# transponder-5_2.net
KiCad netlist of a schematic drawn in EAGLE
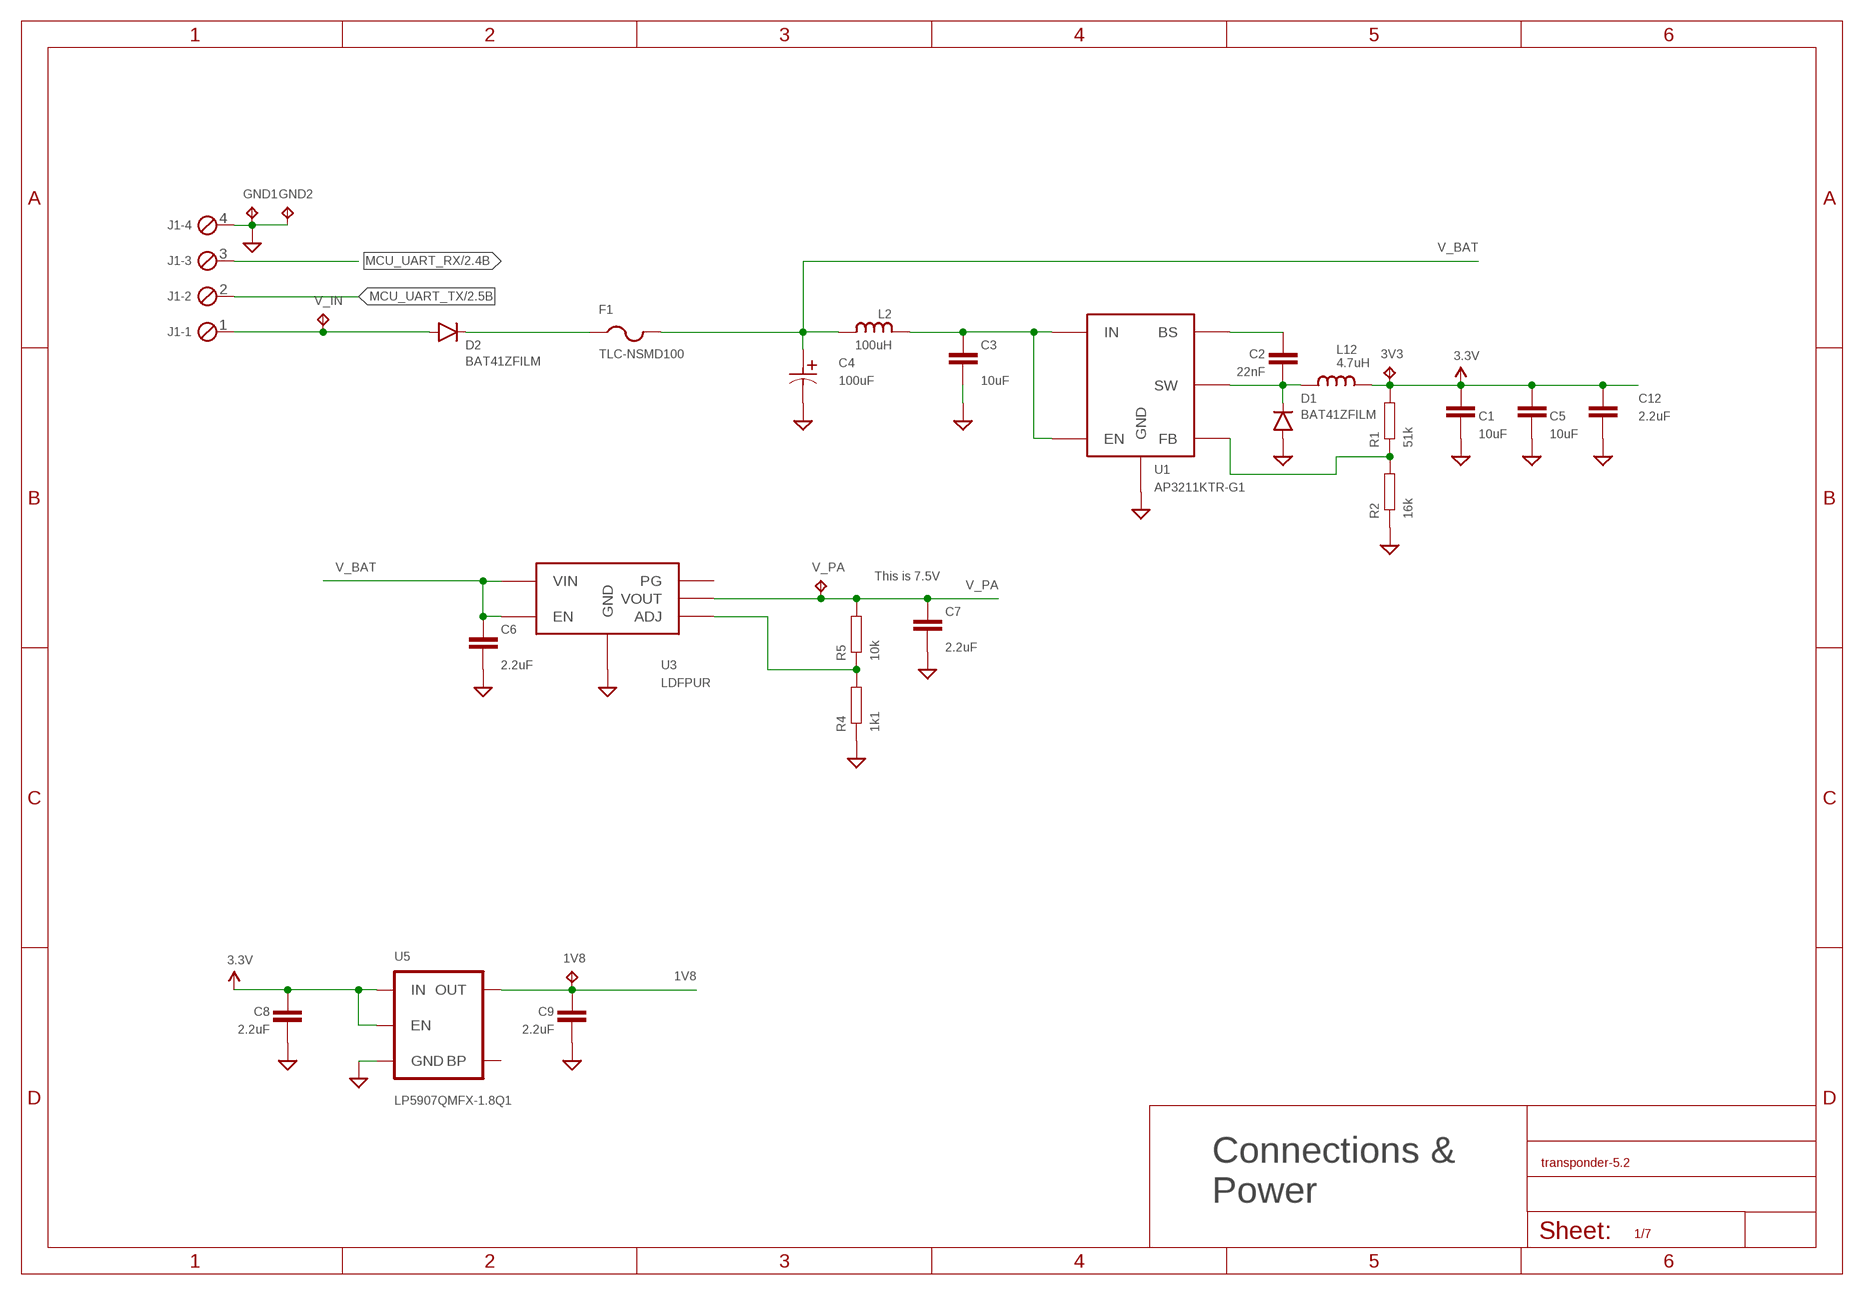
[diagram p0: schematic, sheet 1]
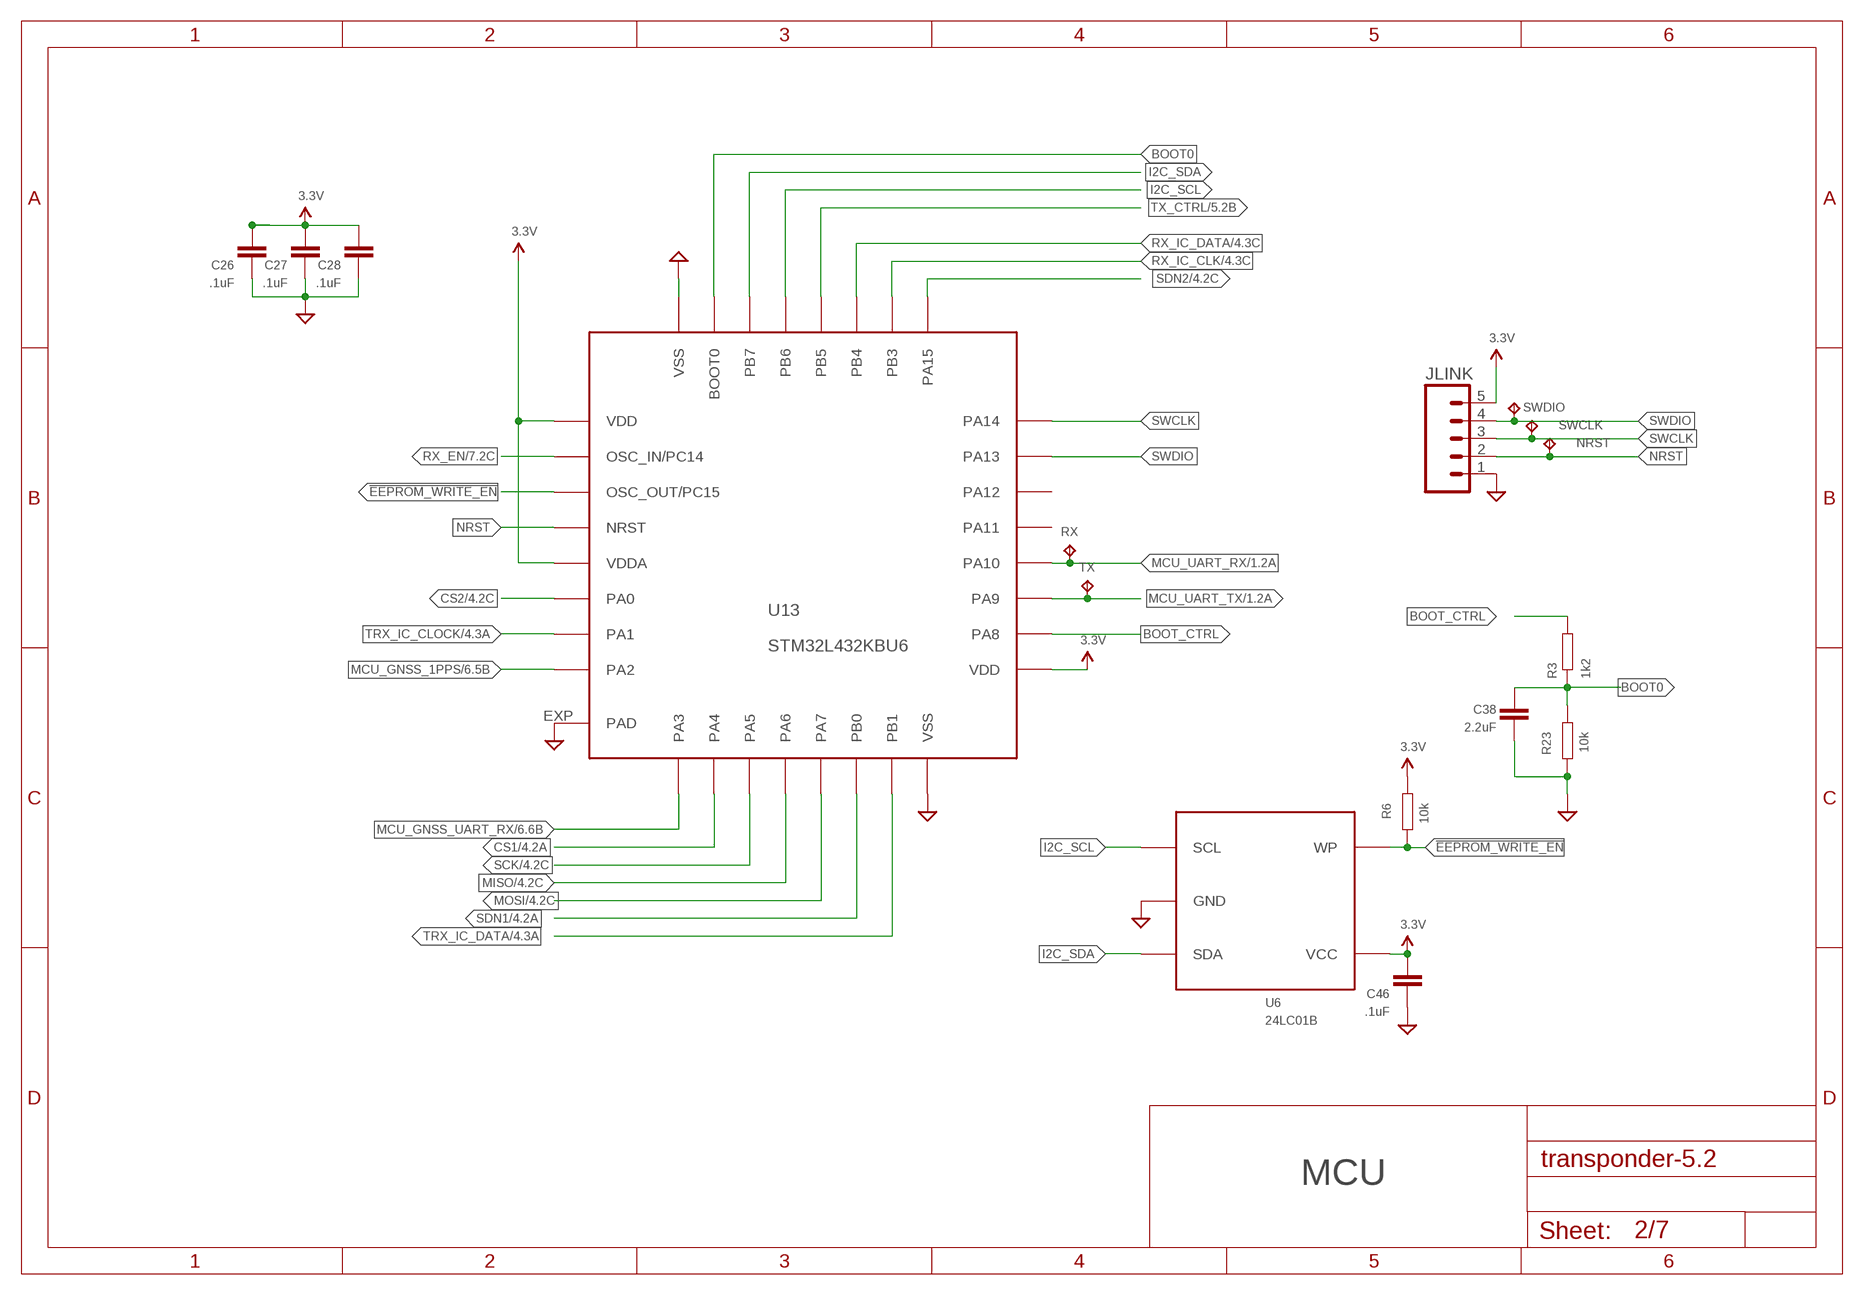
[diagram p1: schematic, sheet 2]
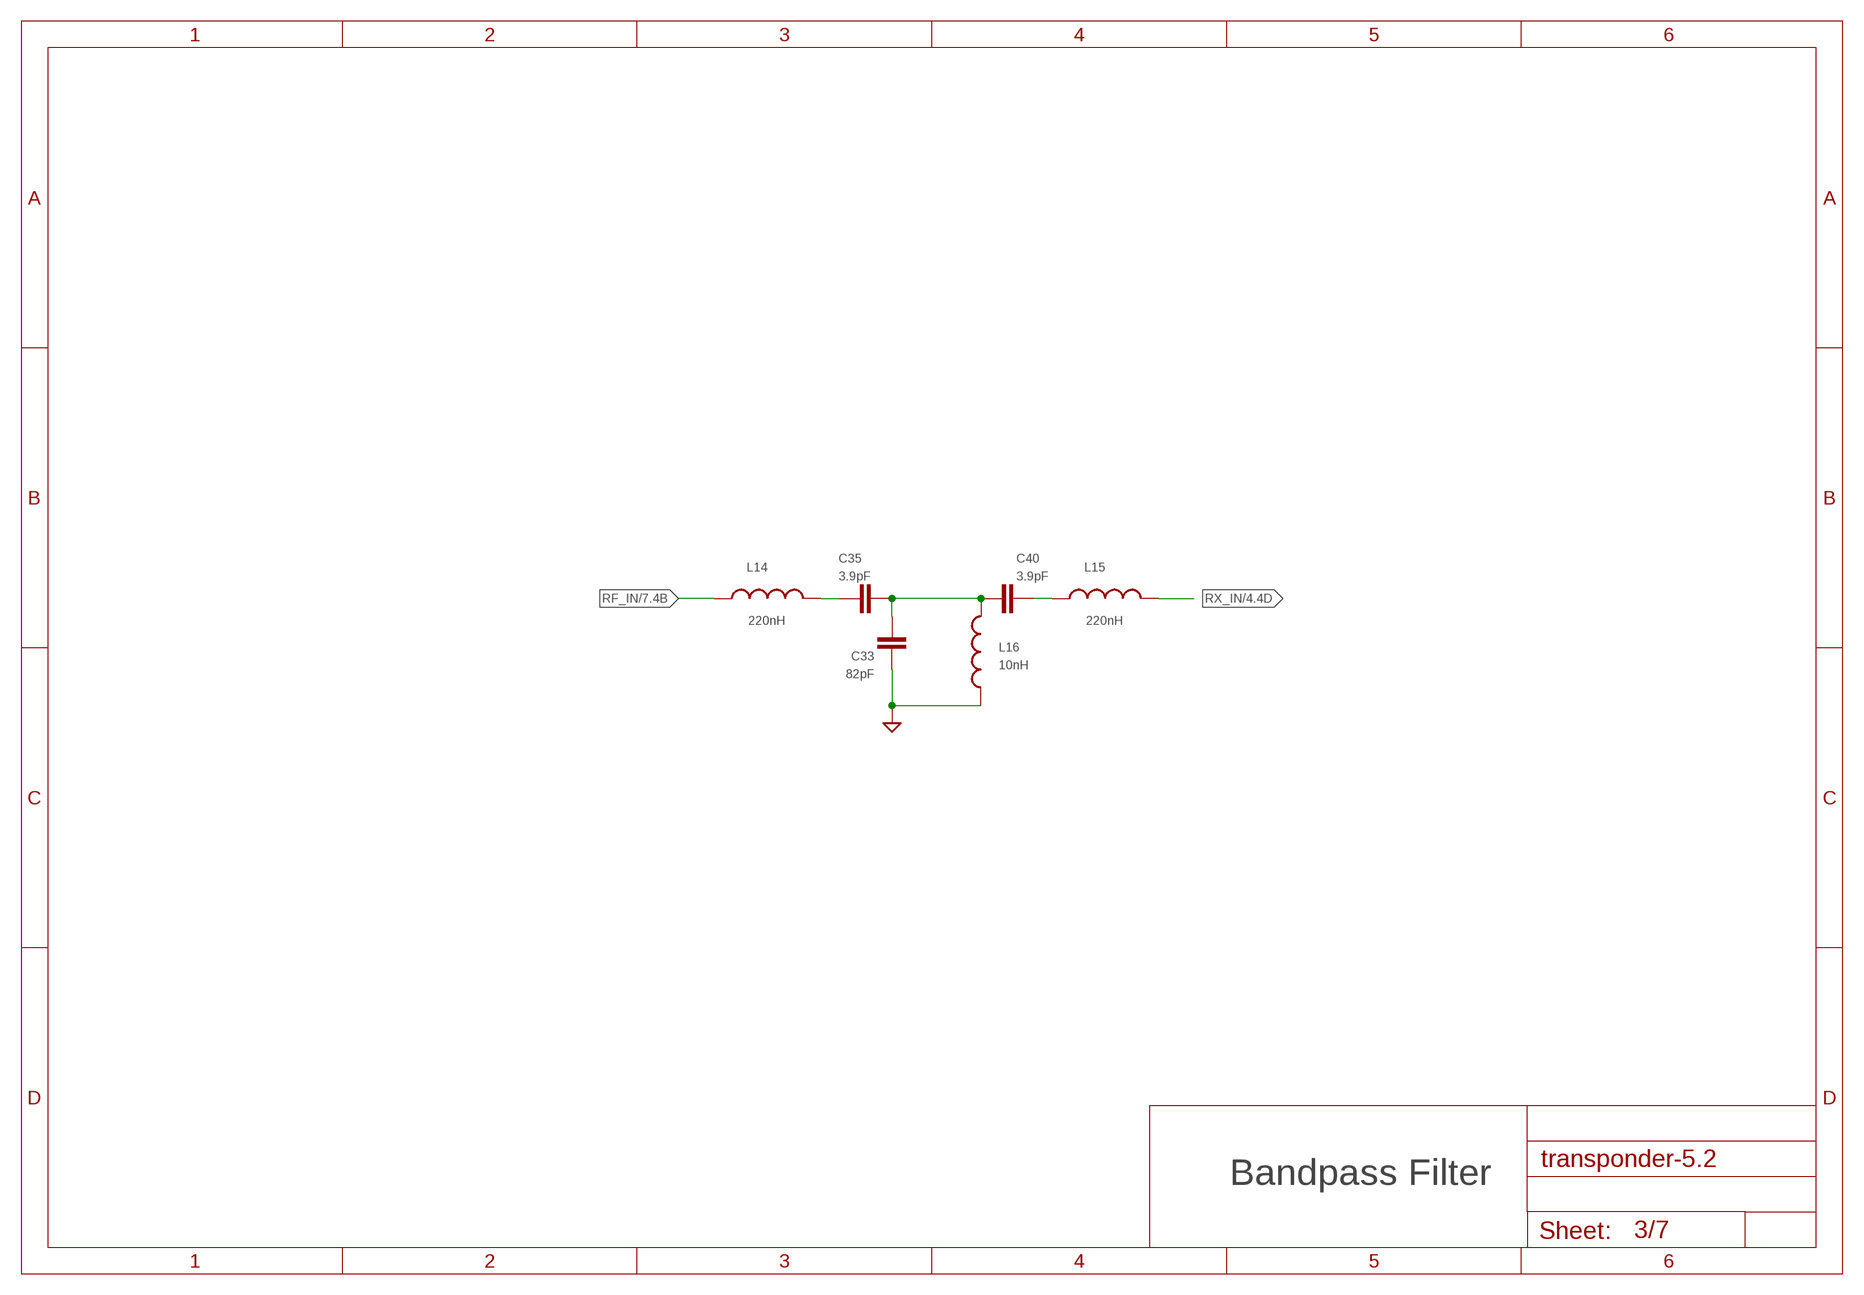
[diagram p2: schematic, sheet 3]
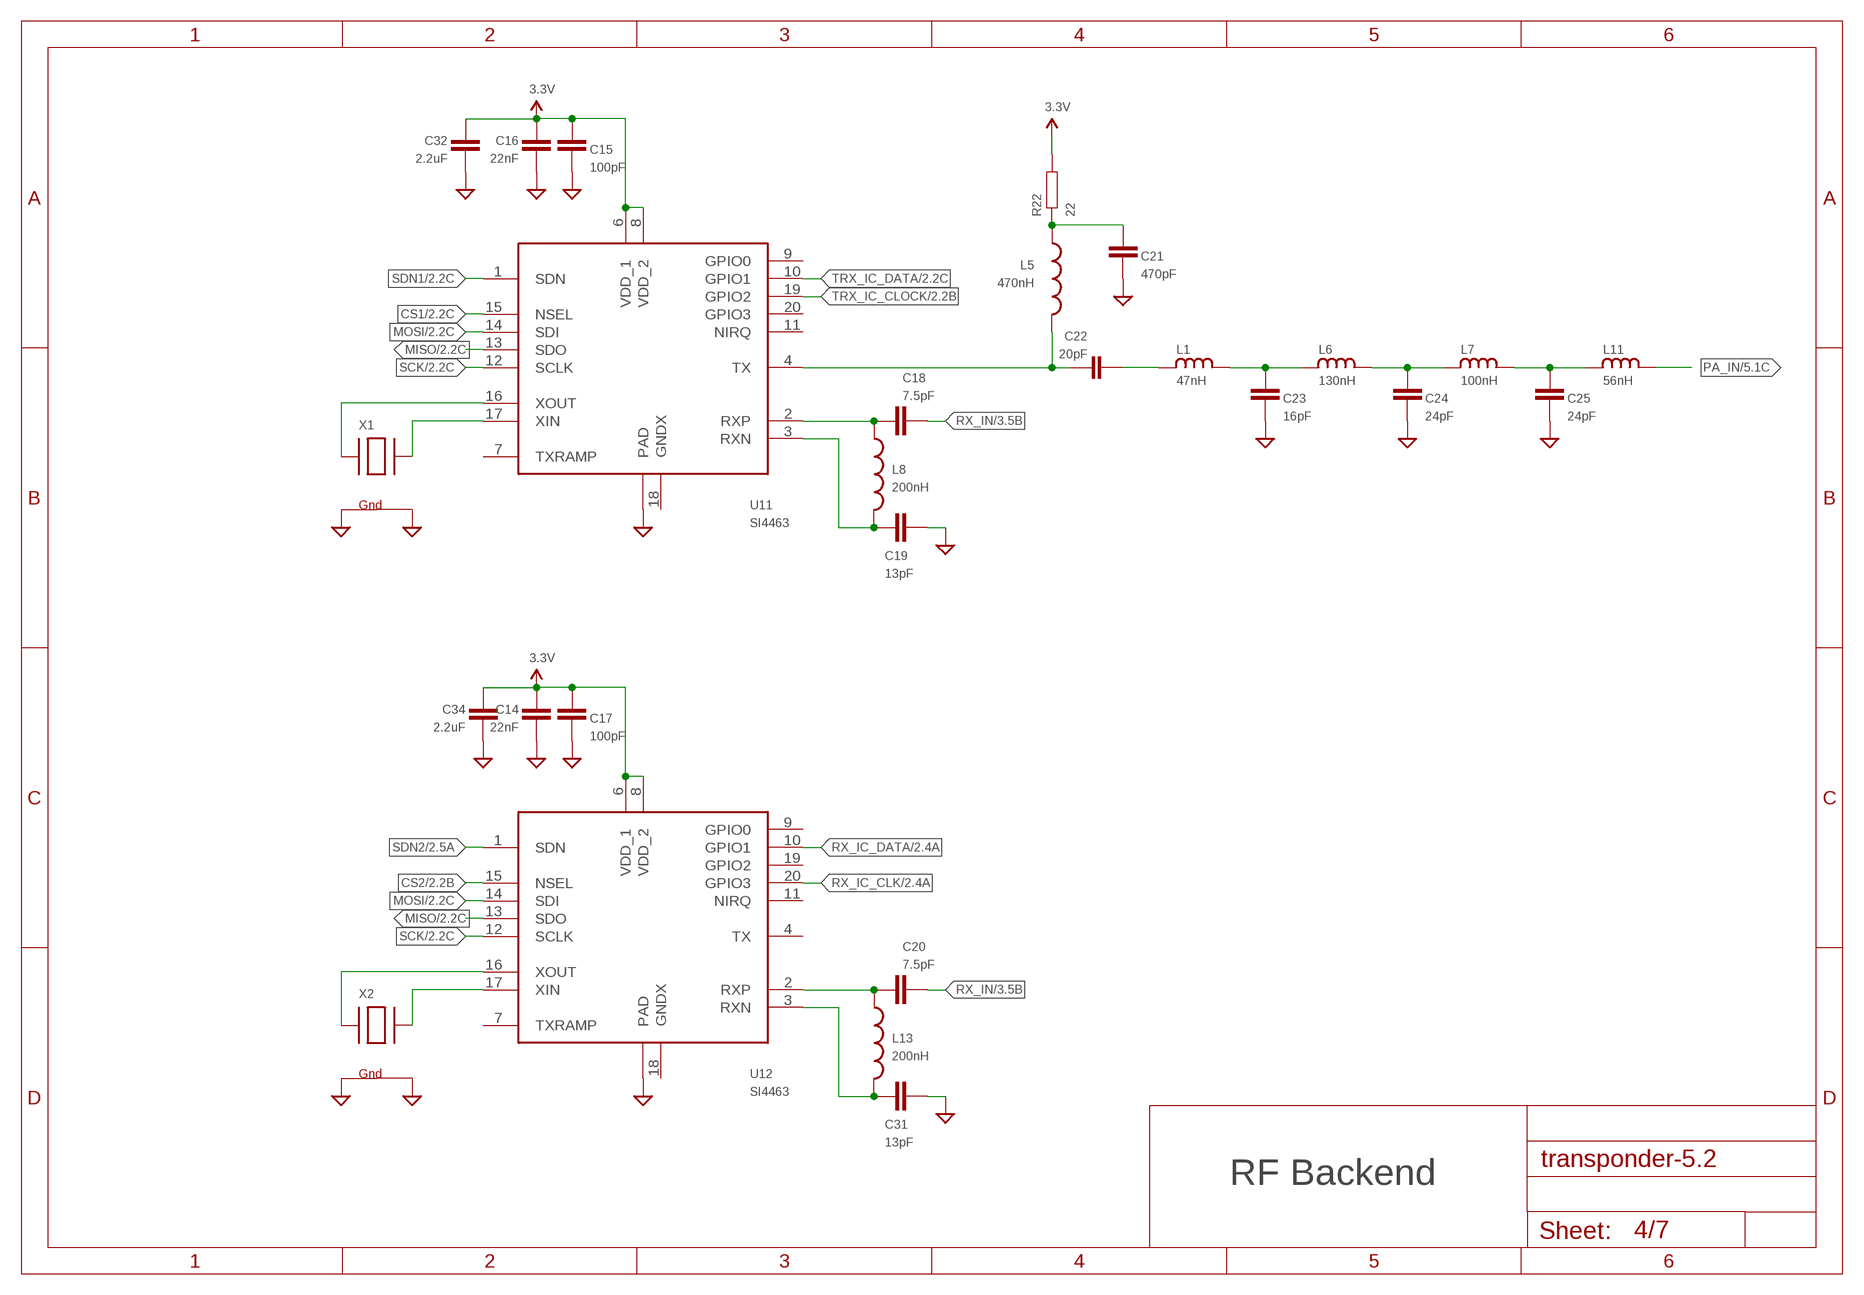
[diagram p3: schematic, sheet 4]
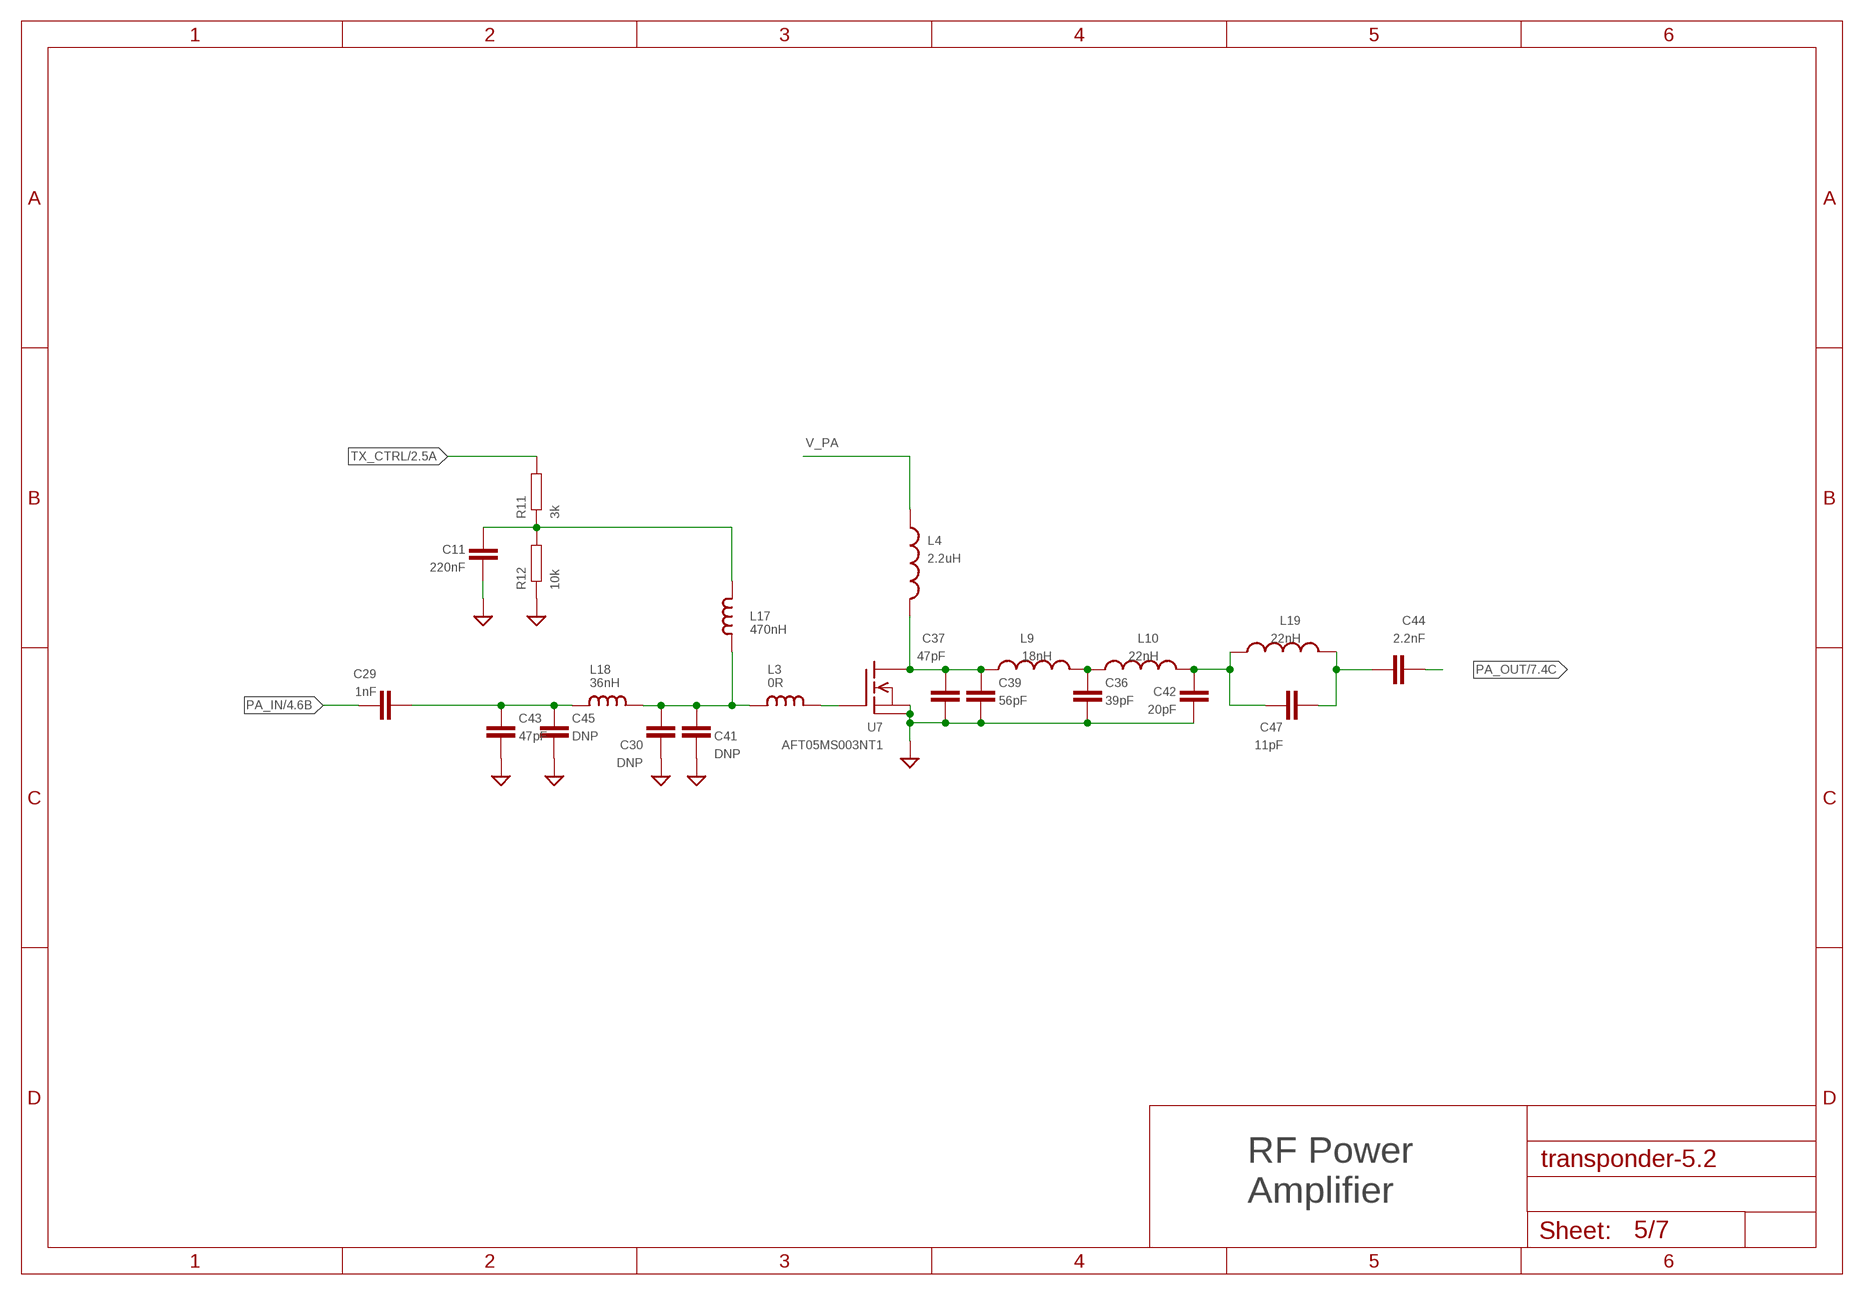
[diagram p4: schematic, sheet 5]
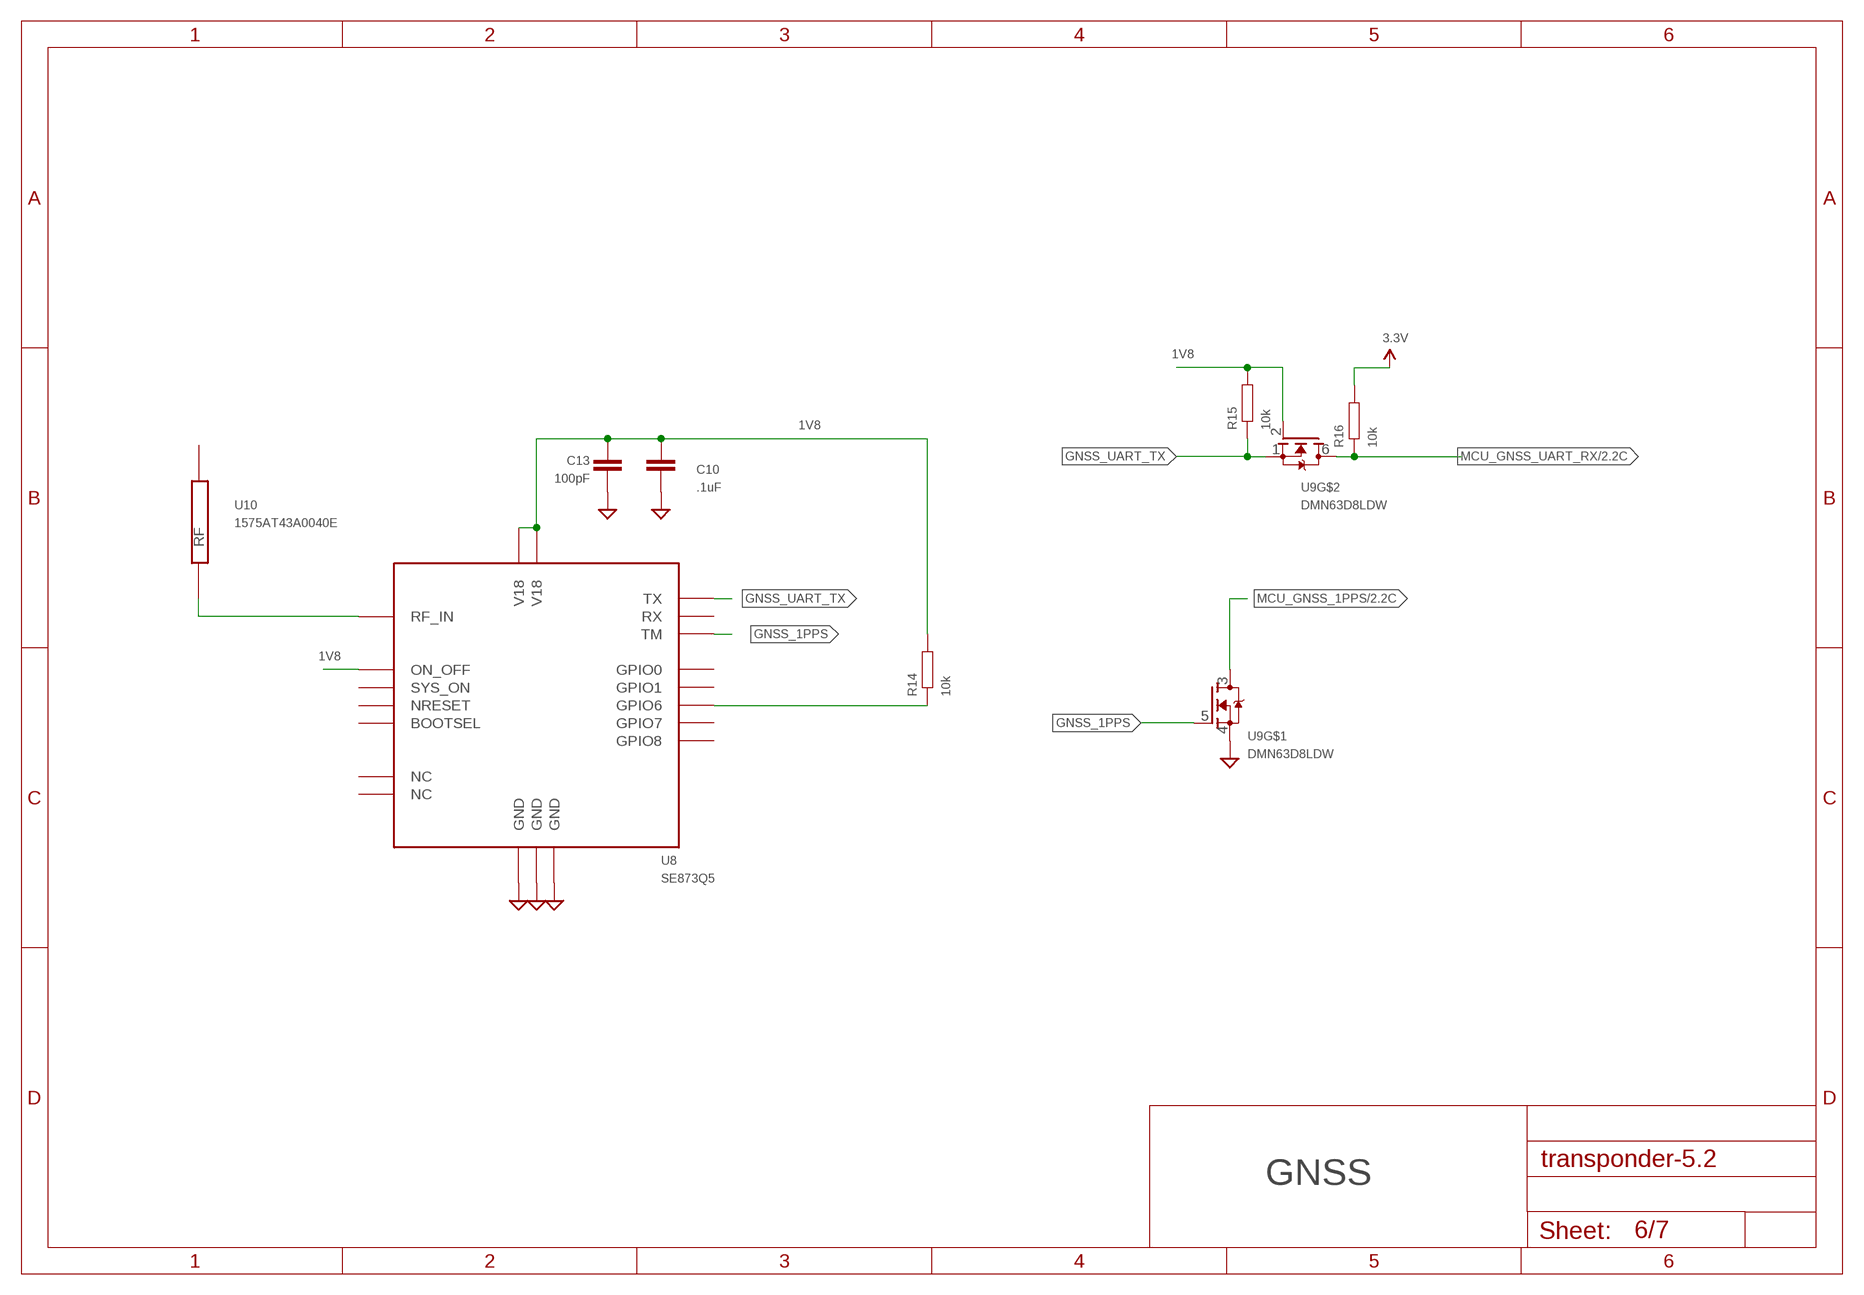
[diagram p5: schematic, sheet 6]
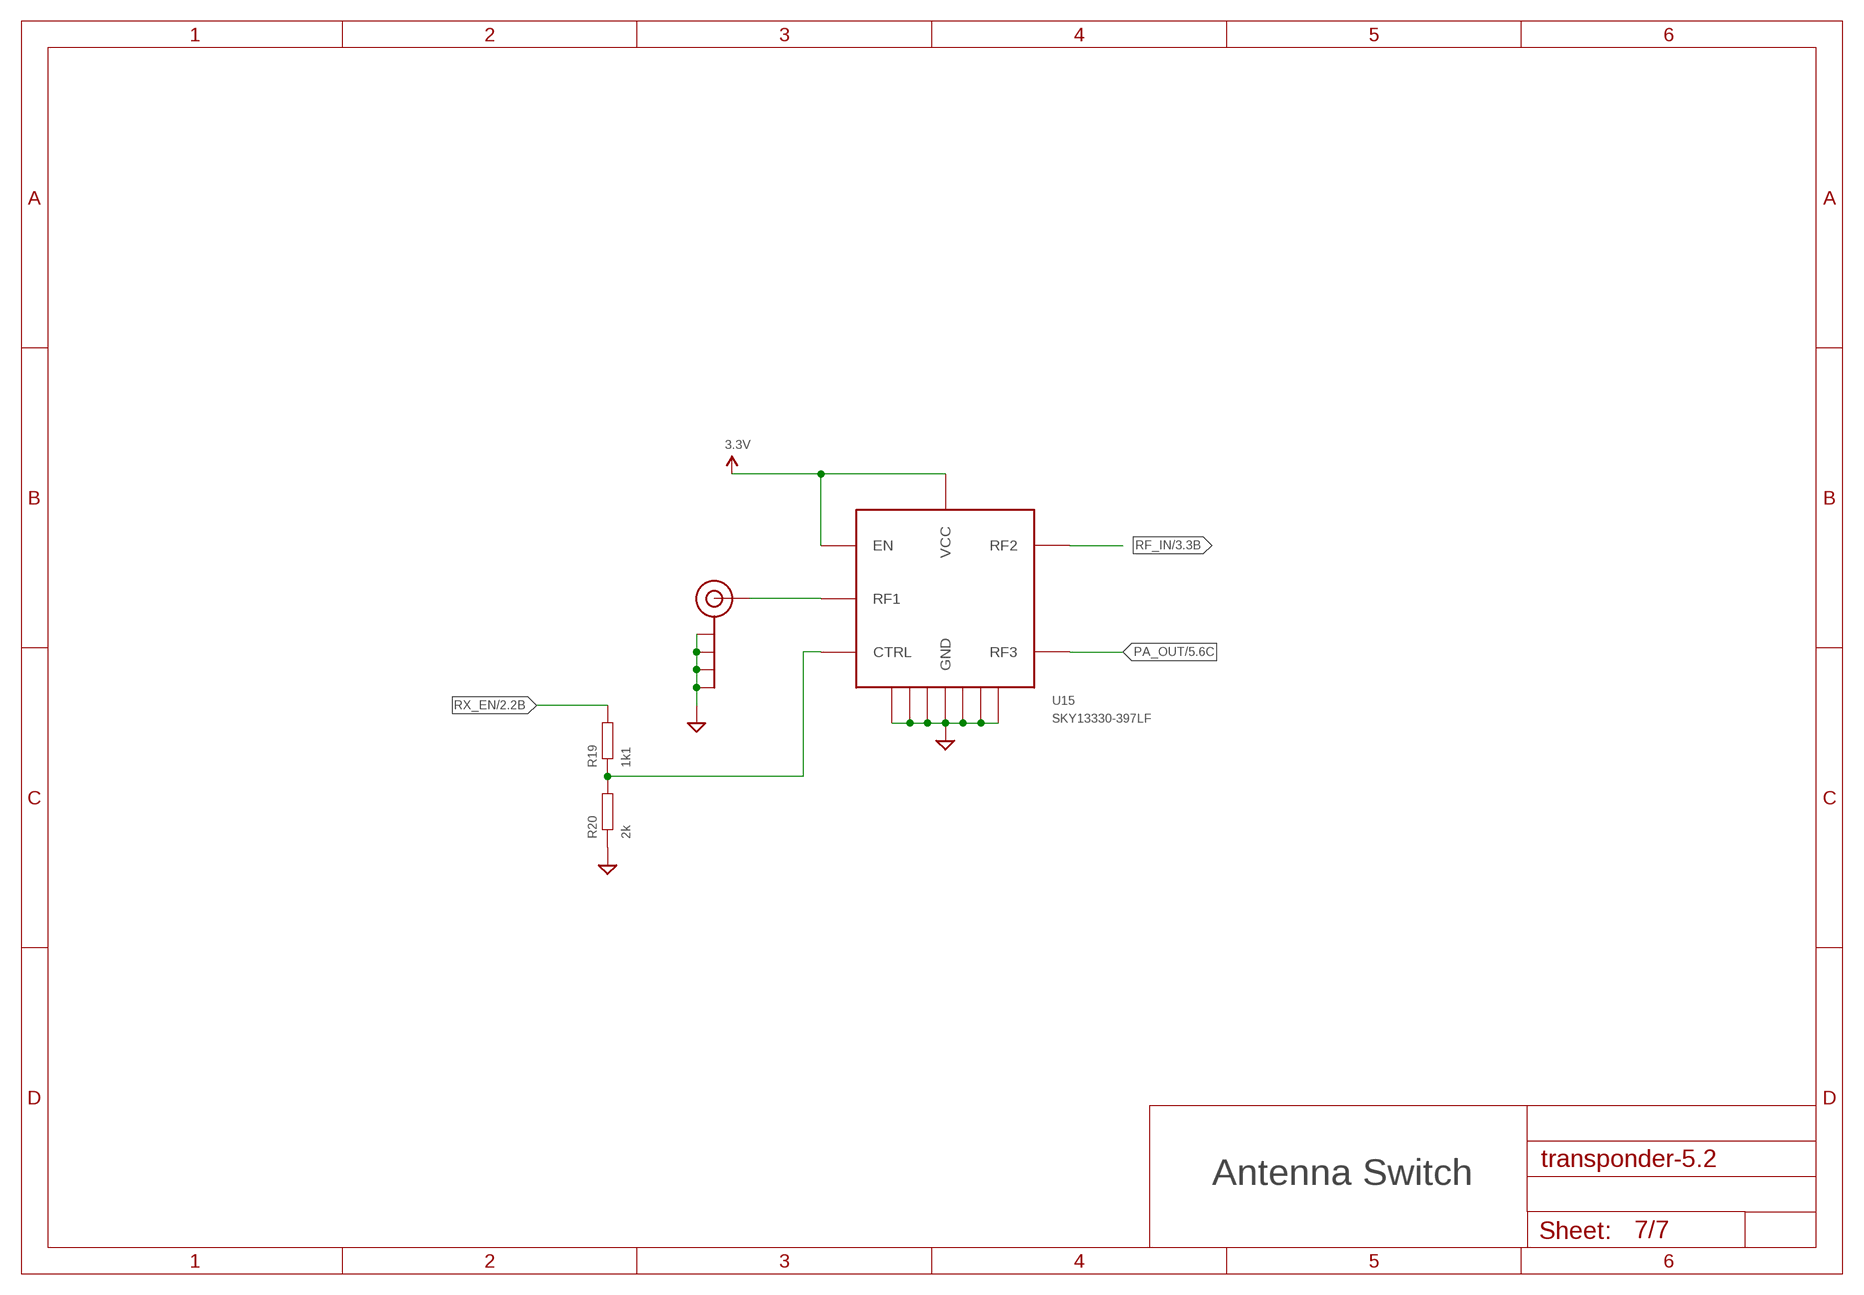
[diagram p6: schematic, sheet 7]

(export (version "E")
  (design (tool "Eeschema 10.0.6"))
  (components
    (comp (ref "J$1")
      (value "SMA_EDGE")
      (footprint "eagle-import:SMA-EDGE")
      (libsource (lib "eagle-import") (part "SMA_EDGE"))
    )
    (comp (ref "R19")
      (value "1k1")
      (footprint "eagle-import:0603-RES")
      (libsource (lib "eagle-import") (part "RESISTOR0603-RES"))
    )
    (comp (ref "R20")
      (value "2k")
      (footprint "eagle-import:0603-RES")
      (fields (field (name "PARTNO") "RC0603FR-072KL"))
      (libsource (lib "eagle-import") (part "RESISTOR0603-RES"))
    )
    (comp (ref "U15")
      (value "SKY13330-397LF")
      (footprint "eagle-import:QFN12")
      (libsource (lib "eagle-import") (part "SKYWORKS-13330397LF"))
    )
    (comp (ref "C33")
      (value "82pF")
      (footprint "eagle-import:0603-CAP")
      (libsource (lib "eagle-import") (part "CAP0603-CAP"))
    )
    (comp (ref "C35")
      (value "3.9pF")
      (footprint "eagle-import:0603-CAP")
      (fields (field (name "PARTNO") "GCM1885C2A3R9BA16D"))
      (libsource (lib "eagle-import") (part "CAP0603-CAP"))
    )
    (comp (ref "C40")
      (value "3.9pF")
      (footprint "eagle-import:0603-CAP")
      (fields (field (name "PARTNO") "GCM1885C2A3R9BA16D"))
      (libsource (lib "eagle-import") (part "CAP0603-CAP"))
    )
    (comp (ref "L14")
      (value "220nH")
      (footprint "eagle-import:0603")
      (libsource (lib "eagle-import") (part "SparkFun-Passives_INDUCTOR0603"))
    )
    (comp (ref "L15")
      (value "220nH")
      (footprint "eagle-import:0603")
      (libsource (lib "eagle-import") (part "SparkFun-Passives_INDUCTOR0603"))
    )
    (comp (ref "L16")
      (value "10nH")
      (footprint "eagle-import:0603")
      (fields (field (name "PARTNO") "LQW18AS10NJ0CD"))
      (libsource (lib "eagle-import") (part "SparkFun-Passives_INDUCTOR0603"))
    )
    (comp (ref "C10")
      (value ".1uF")
      (footprint "eagle-import:0603-CAP")
      (fields (field (name "PARTNO") "EMK107B7104KAHT"))
      (libsource (lib "eagle-import") (part "CAP0603-CAP"))
    )
    (comp (ref "C13")
      (value "100pF")
      (footprint "eagle-import:0603-CAP")
      (fields (field (name "PARTNO") "GCM1885C2A101JA16D"))
      (libsource (lib "eagle-import") (part "CAP0603-CAP"))
    )
    (comp (ref "R14")
      (value "10k")
      (footprint "eagle-import:0603-RES")
      (fields (field (name "PARTNO") "RC0603JR-0710KL"))
      (libsource (lib "eagle-import") (part "RESISTOR0603-RES"))
    )
    (comp (ref "R15")
      (value "10k")
      (footprint "eagle-import:0603-RES")
      (fields (field (name "PARTNO") "RC0603JR-0710KL"))
      (libsource (lib "eagle-import") (part "RESISTOR0603-RES"))
    )
    (comp (ref "R16")
      (value "10k")
      (footprint "eagle-import:0603-RES")
      (fields (field (name "PARTNO") "RC0603JR-0710KL"))
      (libsource (lib "eagle-import") (part "RESISTOR0603-RES"))
    )
    (comp (ref "U8")
      (value "SE873Q5")
      (footprint "eagle-import:SE873")
      (libsource (lib "eagle-import") (part "SE873"))
    )
    (comp (ref "U9")
      (value "DMN63D8LDW")
      (footprint "eagle-import:SOT363")
      (fields (field (name "PARTNO") "DMN63D8LDW"))
      (libsource (lib "eagle-import") (part "DMN63D8LDW"))
    )
    (comp (ref "U10")
      (value "1575AT43A0040E")
      (footprint "eagle-import:1575AT43A0040E")
      (libsource (lib "eagle-import") (part "1575AT43A0040E"))
    )
    (comp (ref "C11")
      (value "220nF")
      (footprint "eagle-import:0603-CAP")
      (libsource (lib "eagle-import") (part "CAP0603-CAP"))
    )
    (comp (ref "C29")
      (value "1nF")
      (footprint "eagle-import:0603-CAP")
      (fields (field (name "PARTNO") "GRM1885C1H102JA01D"))
      (libsource (lib "eagle-import") (part "CAP0603-CAP"))
    )
    (comp (ref "C30")
      (value "DNP")
      (footprint "eagle-import:0603-CAP")
      (fields (field (name "PARTNO") "GCM1885C2A101JA16D"))
      (libsource (lib "eagle-import") (part "CAP0603-CAP"))
    )
    (comp (ref "C36")
      (value "39pF")
      (footprint "eagle-import:0603-CAP")
      (fields (field (name "PARTNO") "GRM1885C1H390JA01D"))
      (libsource (lib "eagle-import") (part "CAP0603-CAP"))
    )
    (comp (ref "C37")
      (value "47pF")
      (footprint "eagle-import:0603-CAP")
      (libsource (lib "eagle-import") (part "CAP0603-CAP"))
    )
    (comp (ref "C39")
      (value "56pF")
      (footprint "eagle-import:0603-CAP")
      (fields (field (name "PARTNO") "GRM1885C1H560JA01D"))
      (libsource (lib "eagle-import") (part "CAP0603-CAP"))
    )
    (comp (ref "C41")
      (value "DNP")
      (footprint "eagle-import:0603-CAP")
      (fields (field (name "PARTNO") "Murata Electronics"))
      (libsource (lib "eagle-import") (part "CAP0603-CAP"))
    )
    (comp (ref "C42")
      (value "20pF")
      (footprint "eagle-import:0603-CAP")
      (fields (field (name "PARTNO") "GRM1885C1H200JA01D"))
      (libsource (lib "eagle-import") (part "CAP0603-CAP"))
    )
    (comp (ref "C43")
      (value "47pF")
      (footprint "eagle-import:0603-CAP")
      (libsource (lib "eagle-import") (part "CAP0603-CAP"))
    )
    (comp (ref "C44")
      (value "2.2nF")
      (footprint "eagle-import:0603-CAP")
      (fields (field (name "PARTNO") "GRM1885C1H222JA01J"))
      (libsource (lib "eagle-import") (part "CAP0603-CAP"))
    )
    (comp (ref "C45")
      (value "DNP")
      (footprint "eagle-import:0603-CAP")
      (fields (field (name "PARTNO") "GRM1885C1H560JA01D"))
      (libsource (lib "eagle-import") (part "CAP0603-CAP"))
    )
    (comp (ref "C47")
      (value "11pF")
      (footprint "eagle-import:0603-CAP")
      (fields (field (name "PARTNO") "GRM1885C1H110JA01D"))
      (libsource (lib "eagle-import") (part "CAP0603-CAP"))
    )
    (comp (ref "L3")
      (value "0R")
      (footprint "eagle-import:0603")
      (fields (field (name "PARTNO") "LQW18AN11NJ00D"))
      (libsource (lib "eagle-import") (part "INDUCTOR0603"))
    )
    (comp (ref "L4")
      (value "2.2uH")
      (footprint "eagle-import:0805")
      (fields (field (name "PARTNO") "BRC2012T2R2MD"))
      (libsource (lib "eagle-import") (part "SparkFun-Passives_INDUCTOR0805"))
    )
    (comp (ref "L9")
      (value "18nH")
      (footprint "eagle-import:0603")
      (fields (field (name "PARTNO") "LQW18AN18NG00D"))
      (libsource (lib "eagle-import") (part "SparkFun-Passives_INDUCTOR0603"))
    )
    (comp (ref "L10")
      (value "22nH")
      (footprint "eagle-import:0603")
      (fields (field (name "PARTNO") "LQW18AN22NJ00D"))
      (libsource (lib "eagle-import") (part "SparkFun-Passives_INDUCTOR0603"))
    )
    (comp (ref "L17")
      (value "470nH")
      (footprint "eagle-import:0603")
      (fields (field (name "PARTNO") "HK1608R47J-T"))
      (libsource (lib "eagle-import") (part "INDUCTOR0603"))
    )
    (comp (ref "L18")
      (value "36nH")
      (footprint "eagle-import:0603")
      (libsource (lib "eagle-import") (part "INDUCTOR0603"))
    )
    (comp (ref "L19")
      (value "22nH")
      (footprint "eagle-import:0603")
      (fields (field (name "PARTNO") "LQW18AN22NJ00D"))
      (libsource (lib "eagle-import") (part "SparkFun-Passives_INDUCTOR0603"))
    )
    (comp (ref "R11")
      (value "3k")
      (footprint "eagle-import:0603-RES")
      (libsource (lib "eagle-import") (part "RESISTOR0603-RES"))
    )
    (comp (ref "R12")
      (value "10k")
      (footprint "eagle-import:0603-RES")
      (fields (field (name "PARTNO") "RC0603JR-0710KL"))
      (libsource (lib "eagle-import") (part "RESISTOR0603-RES"))
    )
    (comp (ref "U7")
      (value "AFT05MS003NT1")
      (footprint "eagle-import:SOT-89")
      (libsource (lib "eagle-import") (part "AFT0SMS003N"))
    )
    (comp (ref "C26")
      (value ".1uF")
      (footprint "eagle-import:0603-CAP")
      (fields (field (name "PARTNO") "EMK107B7104KAHT"))
      (libsource (lib "eagle-import") (part "CAP0603-CAP"))
    )
    (comp (ref "C27")
      (value ".1uF")
      (footprint "eagle-import:0603-CAP")
      (fields (field (name "PARTNO") "EMK107B7104KAHT"))
      (libsource (lib "eagle-import") (part "CAP0603-CAP"))
    )
    (comp (ref "C28")
      (value ".1uF")
      (footprint "eagle-import:0603-CAP")
      (fields (field (name "PARTNO") "EMK107B7104KAHT"))
      (libsource (lib "eagle-import") (part "CAP0603-CAP"))
    )
    (comp (ref "C38")
      (value "2.2uF")
      (footprint "eagle-import:0603-CAP")
      (fields (field (name "PARTNO") "EMK107BJ225KA-T"))
      (libsource (lib "eagle-import") (part "CAP0603-CAP"))
    )
    (comp (ref "C46")
      (value ".1uF")
      (footprint "eagle-import:0603-CAP")
      (fields (field (name "PARTNO") "EMK107B7104KAHT"))
      (libsource (lib "eagle-import") (part "CAP0603-CAP"))
    )
    (comp (ref "JLINK")
      (value "M05PTH")
      (footprint "eagle-import:1X05")
      (libsource (lib "eagle-import") (part "M05PTH"))
    )
    (comp (ref "NRST")
      (value "TPTP16R")
      (footprint "eagle-import:TP16R")
      (libsource (lib "eagle-import") (part "TPTP16R"))
    )
    (comp (ref "R3")
      (value "1k2")
      (footprint "eagle-import:0603-RES")
      (fields (field (name "PARTNO") "RC0603JR-071K2L"))
      (libsource (lib "eagle-import") (part "RESISTOR0603-RES"))
    )
    (comp (ref "R6")
      (value "10k")
      (footprint "eagle-import:0603-RES")
      (fields (field (name "PARTNO") "RC0603JR-0710KL"))
      (libsource (lib "eagle-import") (part "RESISTOR0603-RES"))
    )
    (comp (ref "R23")
      (value "10k")
      (footprint "eagle-import:0603-RES")
      (fields (field (name "PARTNO") "RC0603JR-0710KL"))
      (libsource (lib "eagle-import") (part "RESISTOR0603-RES"))
    )
    (comp (ref "RX")
      (value "TPTP16R")
      (footprint "eagle-import:TP16R")
      (libsource (lib "eagle-import") (part "TPTP16R"))
    )
    (comp (ref "SWCLK")
      (value "TPTP16R")
      (footprint "eagle-import:TP16R")
      (libsource (lib "eagle-import") (part "TPTP16R"))
    )
    (comp (ref "SWDIO")
      (value "TPTP16R")
      (footprint "eagle-import:TP16R")
      (libsource (lib "eagle-import") (part "TPTP16R"))
    )
    (comp (ref "TX")
      (value "TPTP16R")
      (footprint "eagle-import:TP16R")
      (libsource (lib "eagle-import") (part "TPTP16R"))
    )
    (comp (ref "U6")
      (value "24LC01B")
      (footprint "eagle-import:SOT23-5")
      (fields (field (name "PARTNO") "24LC01BT-I/OT"))
      (libsource (lib "eagle-import") (part "24LC01B"))
    )
    (comp (ref "U13")
      (value "STM32L432KBU6")
      (footprint "eagle-import:QFN32")
      (fields (field (name "PARTNO") "STM32L431KBU6"))
      (libsource (lib "eagle-import") (part "STM32L432KXXX"))
    )
    (comp (ref "1V8")
      (value "TPTP16R")
      (footprint "eagle-import:TP16R")
      (libsource (lib "eagle-import") (part "TPTP16R"))
    )
    (comp (ref "3V3")
      (value "TPTP16R")
      (footprint "eagle-import:TP16R")
      (libsource (lib "eagle-import") (part "TPTP16R"))
    )
    (comp (ref "C1")
      (value "10uF")
      (footprint "eagle-import:0805")
      (fields (field (name "PARTNO") " EMK212ABJ106KG-T"))
      (libsource (lib "eagle-import") (part "CAP0805"))
    )
    (comp (ref "C2")
      (value "22nF")
      (footprint "eagle-import:0603-CAP")
      (fields (field (name "PARTNO") "GRM188R71E223KA01D"))
      (libsource (lib "eagle-import") (part "CAP0603-CAP"))
    )
    (comp (ref "C3")
      (value "10uF")
      (footprint "eagle-import:0805")
      (fields (field (name "PARTNO") " EMK212ABJ106KG-T"))
      (libsource (lib "eagle-import") (part "CAP0805"))
    )
    (comp (ref "C4")
      (value "100uF")
      (footprint "eagle-import:PCAP_6.3X5.4-ELECT")
      (fields (field (name "MF") "Nichicon") (field (name "MP") "UWX1C101MCL1GB"))
      (libsource (lib "eagle-import") (part "UWX1C101MCL1GB"))
    )
    (comp (ref "C5")
      (value "10uF")
      (footprint "eagle-import:0805")
      (fields (field (name "PARTNO") " EMK212ABJ106KG-T"))
      (libsource (lib "eagle-import") (part "CAP0805"))
    )
    (comp (ref "C6")
      (value "2.2uF")
      (footprint "eagle-import:0603-CAP")
      (fields (field (name "PARTNO") "EMK107BJ225KA-T"))
      (libsource (lib "eagle-import") (part "CAP0603-CAP"))
    )
    (comp (ref "C7")
      (value "2.2uF")
      (footprint "eagle-import:0603-CAP")
      (fields (field (name "PARTNO") "EMK107BJ225KA-T"))
      (libsource (lib "eagle-import") (part "CAP0603-CAP"))
    )
    (comp (ref "C8")
      (value "2.2uF")
      (footprint "eagle-import:0603-CAP")
      (fields (field (name "PARTNO") "EMK107BJ225KA-T"))
      (libsource (lib "eagle-import") (part "CAP0603-CAP"))
    )
    (comp (ref "C9")
      (value "2.2uF")
      (footprint "eagle-import:0603-CAP")
      (fields (field (name "PARTNO") "EMK107BJ225KA-T"))
      (libsource (lib "eagle-import") (part "CAP0603-CAP"))
    )
    (comp (ref "C12")
      (value "2.2uF")
      (footprint "eagle-import:0603-CAP")
      (fields (field (name "PARTNO") "EMK107BJ225KA-T"))
      (libsource (lib "eagle-import") (part "CAP0603-CAP"))
    )
    (comp (ref "D1")
      (value "BAT41ZFILM")
      (footprint "eagle-import:SOD-123")
      (libsource (lib "eagle-import") (part "DIODESOD123"))
    )
    (comp (ref "D2")
      (value "BAT41ZFILM")
      (footprint "eagle-import:SOD-123")
      (libsource (lib "eagle-import") (part "DIODESOD123"))
    )
    (comp (ref "F1")
      (value "TLC-NSMD100")
      (footprint "eagle-import:R1206")
      (libsource (lib "eagle-import") (part "PTCFUSE-1206"))
    )
    (comp (ref "GND1")
      (value "TPTP16R")
      (footprint "eagle-import:TP16R")
      (libsource (lib "eagle-import") (part "TPTP16R"))
    )
    (comp (ref "GND2")
      (value "TPTP16R")
      (footprint "eagle-import:TP16R")
      (libsource (lib "eagle-import") (part "TPTP16R"))
    )
    (comp (ref "J1")
      (value "MPT4")
      (footprint "eagle-import:4POL254")
      (fields (field (name "DNP") "T"))
      (libsource (lib "eagle-import") (part "MPT4"))
    )
    (comp (ref "L2")
      (value "100uH")
      (footprint "eagle-import:1206")
      (fields (field (name "PARTNO") "CBC3225T101KRV"))
      (libsource (lib "eagle-import") (part "INDUCTOR1206"))
    )
    (comp (ref "L12")
      (value "4.7uH")
      (footprint "eagle-import:0805")
      (fields (field (name "PARTNO") "MLZ2012M4R7WT000"))
      (libsource (lib "eagle-import") (part "INDUCTOR0805"))
    )
    (comp (ref "R1")
      (value "51k")
      (footprint "eagle-import:0603-RES")
      (fields (field (name "PARTNO") "RC0603JR-0751KL"))
      (libsource (lib "eagle-import") (part "RESISTOR0603-RES"))
    )
    (comp (ref "R2")
      (value "16k")
      (footprint "eagle-import:0603-RES")
      (fields (field (name "PARTNO") "RC0603FR-1016KL"))
      (libsource (lib "eagle-import") (part "RESISTOR0603-RES"))
    )
    (comp (ref "R4")
      (value "1k1")
      (footprint "eagle-import:0603-RES")
      (fields (field (name "PARTNO") "RC0603JR-071K1L"))
      (libsource (lib "eagle-import") (part "RESISTOR0603-RES"))
    )
    (comp (ref "R5")
      (value "10k")
      (footprint "eagle-import:0603-RES")
      (fields (field (name "PARTNO") "RC0603JR-0710KL"))
      (libsource (lib "eagle-import") (part "RESISTOR0603-RES"))
    )
    (comp (ref "U1")
      (value "AP3211KTR-G1")
      (footprint "eagle-import:SOT23-6")
      (libsource (lib "eagle-import") (part "AP3211"))
    )
    (comp (ref "U3")
      (value "LDFPUR")
      (footprint "eagle-import:DFN-6")
      (libsource (lib "eagle-import") (part "LDF"))
    )
    (comp (ref "U5")
      (value "LP5907QMFX-1.8Q1")
      (footprint "eagle-import:SOT23-5")
      (fields (field (name "PARTNO") "LP5907QMFX-1.8Q1 "))
      (libsource (lib "eagle-import") (part "V_REG_LDOSMD"))
    )
    (comp (ref "V_IN")
      (value "TPTP16R")
      (footprint "eagle-import:TP16R")
      (libsource (lib "eagle-import") (part "TPTP16R"))
    )
    (comp (ref "V_PA")
      (value "TPTP16R")
      (footprint "eagle-import:TP16R")
      (libsource (lib "eagle-import") (part "TPTP16R"))
    )
    (comp (ref "C14")
      (value "22nF")
      (footprint "eagle-import:0603-CAP")
      (fields (field (name "PARTNO") "GRM188R71E223KA01D"))
      (libsource (lib "eagle-import") (part "CAP0603-CAP"))
    )
    (comp (ref "C15")
      (value "100pF")
      (footprint "eagle-import:0603-CAP")
      (fields (field (name "PARTNO") "GCM1885C2A101JA16D"))
      (libsource (lib "eagle-import") (part "CAP0603-CAP"))
    )
    (comp (ref "C16")
      (value "22nF")
      (footprint "eagle-import:0603-CAP")
      (fields (field (name "PARTNO") "GRM188R71E223KA01D"))
      (libsource (lib "eagle-import") (part "CAP0603-CAP"))
    )
    (comp (ref "C17")
      (value "100pF")
      (footprint "eagle-import:0603-CAP")
      (fields (field (name "PARTNO") "GCM1885C2A101JA16D"))
      (libsource (lib "eagle-import") (part "CAP0603-CAP"))
    )
    (comp (ref "C18")
      (value "7.5pF")
      (footprint "eagle-import:0603-CAP")
      (fields (field (name "PARTNO") "GRM1885C1H7R5DA01D"))
      (libsource (lib "eagle-import") (part "CAP0603-CAP"))
    )
    (comp (ref "C19")
      (value "13pF")
      (footprint "eagle-import:0603-CAP")
      (fields (field (name "PARTNO") "GRM1885C1H130JA01D"))
      (libsource (lib "eagle-import") (part "CAP0603-CAP"))
    )
    (comp (ref "C20")
      (value "7.5pF")
      (footprint "eagle-import:0603-CAP")
      (fields (field (name "PARTNO") "GRM1885C1H7R5DA01D"))
      (libsource (lib "eagle-import") (part "CAP0603-CAP"))
    )
    (comp (ref "C21")
      (value "470pF")
      (footprint "eagle-import:0603-CAP")
      (fields (field (name "PARTNO") "GCM1885C2A471JA16J"))
      (libsource (lib "eagle-import") (part "CAP0603-CAP"))
    )
    (comp (ref "C22")
      (value "20pF")
      (footprint "eagle-import:0603")
      (fields (field (name "PARTNO") "GRM1885C1H200JA01D"))
      (libsource (lib "eagle-import") (part "CAPACITOR0603"))
    )
    (comp (ref "C23")
      (value "16pF")
      (footprint "eagle-import:0603-CAP")
      (fields (field (name "PARTNO") "GCM1885C2A160JA16D"))
      (libsource (lib "eagle-import") (part "CAP0603-CAP"))
    )
    (comp (ref "C24")
      (value "24pF")
      (footprint "eagle-import:0603-CAP")
      (fields (field (name "PARTNO") "GCM1885C2A240JA16D"))
      (libsource (lib "eagle-import") (part "CAP0603-CAP"))
    )
    (comp (ref "C25")
      (value "24pF")
      (footprint "eagle-import:0603-CAP")
      (fields (field (name "PARTNO") "GCM1885C2A240JA16D"))
      (libsource (lib "eagle-import") (part "CAP0603-CAP"))
    )
    (comp (ref "C31")
      (value "13pF")
      (footprint "eagle-import:0603-CAP")
      (fields (field (name "PARTNO") "GRM1885C1H130JA01D"))
      (libsource (lib "eagle-import") (part "CAP0603-CAP"))
    )
    (comp (ref "C32")
      (value "2.2uF")
      (footprint "eagle-import:0603-CAP")
      (fields (field (name "PARTNO") "EMK107BJ225KA-T"))
      (libsource (lib "eagle-import") (part "CAP0603-CAP"))
    )
    (comp (ref "C34")
      (value "2.2uF")
      (footprint "eagle-import:0603-CAP")
      (fields (field (name "PARTNO") "EMK107BJ225KA-T"))
      (libsource (lib "eagle-import") (part "CAP0603-CAP"))
    )
    (comp (ref "L1")
      (value "47nH")
      (footprint "eagle-import:0603")
      (fields (field (name "PARTNO") "LQW18AS47NG00D"))
      (libsource (lib "eagle-import") (part "INDUCTOR0603"))
    )
    (comp (ref "L5")
      (value "470nH")
      (footprint "eagle-import:0603")
      (fields (field (name "PARTNO") "HK1608R47J-T"))
      (libsource (lib "eagle-import") (part "SparkFun-Passives_INDUCTOR0603"))
    )
    (comp (ref "L6")
      (value "130nH")
      (footprint "eagle-import:0603")
      (fields (field (name "PARTNO") "LQW18ANR13G00D"))
      (libsource (lib "eagle-import") (part "INDUCTOR0603"))
    )
    (comp (ref "L7")
      (value "100nH")
      (footprint "eagle-import:0603")
      (fields (field (name "PARTNO") "LQW18ANR10G00D"))
      (libsource (lib "eagle-import") (part "INDUCTOR0603"))
    )
    (comp (ref "L8")
      (value "200nH")
      (footprint "eagle-import:0603")
      (fields (field (name "PARTNO") "LQW18ANR20J00D"))
      (libsource (lib "eagle-import") (part "SparkFun-Passives_INDUCTOR0603"))
    )
    (comp (ref "L11")
      (value "56nH")
      (footprint "eagle-import:0603")
      (fields (field (name "PARTNO") "LQW18AN56NG00D"))
      (libsource (lib "eagle-import") (part "INDUCTOR0603"))
    )
    (comp (ref "L13")
      (value "200nH")
      (footprint "eagle-import:0603")
      (fields (field (name "PARTNO") "LQW18ANR20J00D"))
      (libsource (lib "eagle-import") (part "SparkFun-Passives_INDUCTOR0603"))
    )
    (comp (ref "R22")
      (value "22")
      (footprint "eagle-import:0603-RES")
      (fields (field (name "PARTNO") "RC0603JR-0722RL"))
      (libsource (lib "eagle-import") (part "RESISTOR0603-RES"))
    )
    (comp (ref "U11")
      (value "SI4463")
      (footprint "eagle-import:SI4463")
      (fields (field (name "PARTNO") "SI4463-C2A-GMR"))
      (libsource (lib "eagle-import") (part "SI4463"))
    )
    (comp (ref "U12")
      (value "SI4463")
      (footprint "eagle-import:SI4463")
      (fields (field (name "PARTNO") "SI4463-C2A-GMR"))
      (libsource (lib "eagle-import") (part "SI4463"))
    )
    (comp (ref "X1")
      (value "XTAL-4-3225")
      (footprint "eagle-import:NX3225")
      (fields (field (name "PARTNO") "CX3225SB30000D0FPLCC"))
      (libsource (lib "eagle-import") (part "XTAL-4-3225"))
    )
    (comp (ref "X2")
      (value "XTAL-4-3225")
      (footprint "eagle-import:NX3225")
      (fields (field (name "PARTNO") "CX3225SB30000D0FPLCC"))
      (libsource (lib "eagle-import") (part "XTAL-4-3225"))
    )
  )
  (nets
    (net (code "1") (name "1V8") (class "Default")
      (node (ref "1V8") (pin "TP") (pinfunction "TP_TP") (pintype "input"))
      (node (ref "C10") (pin "1") (pinfunction "1_1") (pintype "passive"))
      (node (ref "C13") (pin "1") (pinfunction "1_1") (pintype "passive"))
      (node (ref "C9") (pin "1") (pinfunction "1_1") (pintype "passive"))
      (node (ref "R14") (pin "2") (pinfunction "2_2") (pintype "passive"))
      (node (ref "R15") (pin "2") (pinfunction "2_2") (pintype "passive"))
      (node (ref "U5") (pin "5") (pinfunction "OUT_5") (pintype "passive"))
      (node (ref "U8") (pin "P$19") (pinfunction "V18_P$19") (pintype "bidirectional"))
      (node (ref "U8") (pin "P$3") (pinfunction "V18_P$3") (pintype "bidirectional"))
      (node (ref "U8") (pin "P$6") (pinfunction "ON_OFF_P$6") (pintype "bidirectional"))
      (node (ref "U9") (pin "2") (pinfunction "G_2") (pintype "bidirectional"))
    )
    (net (code "2") (name "3.3V") (class "Default")
      (node (ref "3V3") (pin "TP") (pinfunction "TP_TP") (pintype "input"))
      (node (ref "C1") (pin "1") (pinfunction "1_1") (pintype "passive"))
      (node (ref "C12") (pin "1") (pinfunction "1_1") (pintype "passive"))
      (node (ref "C14") (pin "1") (pinfunction "1_1") (pintype "passive"))
      (node (ref "C15") (pin "1") (pinfunction "1_1") (pintype "passive"))
      (node (ref "C16") (pin "1") (pinfunction "1_1") (pintype "passive"))
      (node (ref "C17") (pin "1") (pinfunction "1_1") (pintype "passive"))
      (node (ref "C26") (pin "1") (pinfunction "1_1") (pintype "passive"))
      (node (ref "C27") (pin "1") (pinfunction "1_1") (pintype "passive"))
      (node (ref "C28") (pin "1") (pinfunction "1_1") (pintype "passive"))
      (node (ref "C32") (pin "1") (pinfunction "1_1") (pintype "passive"))
      (node (ref "C34") (pin "1") (pinfunction "1_1") (pintype "passive"))
      (node (ref "C46") (pin "1") (pinfunction "1_1") (pintype "passive"))
      (node (ref "C5") (pin "1") (pinfunction "1_1") (pintype "passive"))
      (node (ref "C8") (pin "1") (pinfunction "1_1") (pintype "passive"))
      (node (ref "JLINK") (pin "5") (pinfunction "5_5") (pintype "passive"))
      (node (ref "L12") (pin "P$2") (pinfunction "P$2_P$2") (pintype "bidirectional"))
      (node (ref "R1") (pin "2") (pinfunction "2_2") (pintype "passive"))
      (node (ref "R16") (pin "2") (pinfunction "2_2") (pintype "passive"))
      (node (ref "R22") (pin "2") (pinfunction "2_2") (pintype "passive"))
      (node (ref "R6") (pin "1") (pinfunction "1_1") (pintype "passive"))
      (node (ref "U11") (pin "6") (pinfunction "VDD_1_6") (pintype "power_in"))
      (node (ref "U11") (pin "8") (pinfunction "VDD_2_8") (pintype "power_in"))
      (node (ref "U12") (pin "6") (pinfunction "VDD_1_6") (pintype "power_in"))
      (node (ref "U12") (pin "8") (pinfunction "VDD_2_8") (pintype "power_in"))
      (node (ref "U13") (pin "1") (pinfunction "VDD_1") (pintype "bidirectional"))
      (node (ref "U13") (pin "17") (pinfunction "VDD_17") (pintype "bidirectional"))
      (node (ref "U13") (pin "5") (pinfunction "VDDA_5") (pintype "bidirectional"))
      (node (ref "U15") (pin "P$8") (pinfunction "EN_P$8") (pintype "bidirectional"))
      (node (ref "U15") (pin "P$9") (pinfunction "VCC_P$9") (pintype "bidirectional"))
      (node (ref "U5") (pin "1") (pinfunction "IN_1") (pintype "input"))
      (node (ref "U5") (pin "3") (pinfunction "EN_3") (pintype "input"))
      (node (ref "U6") (pin "4") (pinfunction "VCC_4") (pintype "bidirectional"))
    )
    (net (code "3") (name "BOOT0") (class "Default")
      (node (ref "C38") (pin "1") (pinfunction "1_1") (pintype "passive"))
      (node (ref "R23") (pin "1") (pinfunction "1_1") (pintype "passive"))
      (node (ref "R3") (pin "1") (pinfunction "1_1") (pintype "passive"))
      (node (ref "U13") (pin "31") (pinfunction "BOOT0_31") (pintype "bidirectional"))
    )
    (net (code "4") (name "BOOT_CTRL") (class "Default")
      (node (ref "R3") (pin "2") (pinfunction "2_2") (pintype "passive"))
      (node (ref "U13") (pin "18") (pinfunction "PA8_18") (pintype "bidirectional"))
    )
    (net (code "5") (name "CS1") (class "Default")
      (node (ref "U11") (pin "15") (pinfunction "NSEL_15") (pintype "input"))
      (node (ref "U13") (pin "10") (pinfunction "PA4_10") (pintype "bidirectional"))
    )
    (net (code "6") (name "CS2") (class "Default")
      (node (ref "U12") (pin "15") (pinfunction "NSEL_15") (pintype "input"))
      (node (ref "U13") (pin "6") (pinfunction "PA0_6") (pintype "bidirectional"))
    )
    (net (code "7") (name "GND") (class "Default")
      (node (ref "C1") (pin "2") (pinfunction "2_2") (pintype "passive"))
      (node (ref "C10") (pin "2") (pinfunction "2_2") (pintype "passive"))
      (node (ref "C11") (pin "2") (pinfunction "2_2") (pintype "passive"))
      (node (ref "C12") (pin "2") (pinfunction "2_2") (pintype "passive"))
      (node (ref "C13") (pin "2") (pinfunction "2_2") (pintype "passive"))
      (node (ref "C14") (pin "2") (pinfunction "2_2") (pintype "passive"))
      (node (ref "C15") (pin "2") (pinfunction "2_2") (pintype "passive"))
      (node (ref "C16") (pin "2") (pinfunction "2_2") (pintype "passive"))
      (node (ref "C17") (pin "2") (pinfunction "2_2") (pintype "passive"))
      (node (ref "C19") (pin "1") (pinfunction "1_1") (pintype "passive"))
      (node (ref "C21") (pin "2") (pinfunction "2_2") (pintype "passive"))
      (node (ref "C23") (pin "2") (pinfunction "2_2") (pintype "passive"))
      (node (ref "C24") (pin "2") (pinfunction "2_2") (pintype "passive"))
      (node (ref "C25") (pin "2") (pinfunction "2_2") (pintype "passive"))
      (node (ref "C26") (pin "2") (pinfunction "2_2") (pintype "passive"))
      (node (ref "C27") (pin "2") (pinfunction "2_2") (pintype "passive"))
      (node (ref "C28") (pin "2") (pinfunction "2_2") (pintype "passive"))
      (node (ref "C3") (pin "2") (pinfunction "2_2") (pintype "passive"))
      (node (ref "C30") (pin "2") (pinfunction "2_2") (pintype "passive"))
      (node (ref "C31") (pin "1") (pinfunction "1_1") (pintype "passive"))
      (node (ref "C32") (pin "2") (pinfunction "2_2") (pintype "passive"))
      (node (ref "C33") (pin "1") (pinfunction "1_1") (pintype "passive"))
      (node (ref "C34") (pin "2") (pinfunction "2_2") (pintype "passive"))
      (node (ref "C36") (pin "2") (pinfunction "2_2") (pintype "passive"))
      (node (ref "C37") (pin "2") (pinfunction "2_2") (pintype "passive"))
      (node (ref "C38") (pin "2") (pinfunction "2_2") (pintype "passive"))
      (node (ref "C39") (pin "2") (pinfunction "2_2") (pintype "passive"))
      (node (ref "C4") (pin "2") (pinfunction "22_2") (pintype "passive"))
      (node (ref "C41") (pin "2") (pinfunction "2_2") (pintype "passive"))
      (node (ref "C42") (pin "2") (pinfunction "2_2") (pintype "passive"))
      (node (ref "C43") (pin "2") (pinfunction "2_2") (pintype "passive"))
      (node (ref "C45") (pin "2") (pinfunction "2_2") (pintype "passive"))
      (node (ref "C46") (pin "2") (pinfunction "2_2") (pintype "passive"))
      (node (ref "C5") (pin "2") (pinfunction "2_2") (pintype "passive"))
      (node (ref "C6") (pin "2") (pinfunction "2_2") (pintype "passive"))
      (node (ref "C7") (pin "2") (pinfunction "2_2") (pintype "passive"))
      (node (ref "C8") (pin "2") (pinfunction "2_2") (pintype "passive"))
      (node (ref "C9") (pin "2") (pinfunction "2_2") (pintype "passive"))
      (node (ref "D1") (pin "A") (pinfunction "A_A") (pintype "passive"))
      (node (ref "GND1") (pin "TP") (pinfunction "TP_TP") (pintype "input"))
      (node (ref "GND2") (pin "TP") (pinfunction "TP_TP") (pintype "input"))
      (node (ref "J$1") (pin "GND@0") (pinfunction "GND_GND@0") (pintype "bidirectional"))
      (node (ref "J$1") (pin "GND@1") (pinfunction "GND_GND@1") (pintype "bidirectional"))
      (node (ref "J$1") (pin "GND@2") (pinfunction "GND_GND@2") (pintype "bidirectional"))
      (node (ref "J$1") (pin "GND@3") (pinfunction "GND_GND@3") (pintype "bidirectional"))
      (node (ref "J1") (pin "4") (pinfunction "1_4") (pintype "passive"))
      (node (ref "JLINK") (pin "1") (pinfunction "1_1") (pintype "passive"))
      (node (ref "L16") (pin "1") (pinfunction "1_1") (pintype "passive"))
      (node (ref "R12") (pin "1") (pinfunction "1_1") (pintype "passive"))
      (node (ref "R2") (pin "1") (pinfunction "1_1") (pintype "passive"))
      (node (ref "R20") (pin "1") (pinfunction "1_1") (pintype "passive"))
      (node (ref "R23") (pin "2") (pinfunction "2_2") (pintype "passive"))
      (node (ref "R4") (pin "1") (pinfunction "1_1") (pintype "passive"))
      (node (ref "U1") (pin "2") (pinfunction "GND_2") (pintype "bidirectional"))
      (node (ref "U11") (pin "EXP") (pinfunction "PAD_EXP") (pintype "bidirectional"))
      (node (ref "U12") (pin "EXP") (pinfunction "PAD_EXP") (pintype "bidirectional"))
      (node (ref "U13") (pin "16") (pinfunction "VSS_16") (pintype "bidirectional"))
      (node (ref "U13") (pin "32") (pinfunction "VSS_32") (pintype "bidirectional"))
      (node (ref "U13") (pin "EXP") (pinfunction "PAD_EXP") (pintype "bidirectional"))
      (node (ref "U15") (pin "P$1") (pinfunction "GND_P$1") (pintype "bidirectional"))
      (node (ref "U15") (pin "P$10") (pinfunction "GND_P$10") (pintype "bidirectional"))
      (node (ref "U15") (pin "P$12") (pinfunction "GND_P$12") (pintype "bidirectional"))
      (node (ref "U15") (pin "P$13") (pinfunction "GND_P$13") (pintype "bidirectional"))
      (node (ref "U15") (pin "P$3") (pinfunction "GND_P$3") (pintype "bidirectional"))
      (node (ref "U15") (pin "P$4") (pinfunction "GND_P$4") (pintype "bidirectional"))
      (node (ref "U15") (pin "P$6") (pinfunction "GND_P$6") (pintype "bidirectional"))
      (node (ref "U3") (pin "P$4") (pinfunction "GND_P$4") (pintype "bidirectional"))
      (node (ref "U3") (pin "P$7") (pinfunction "GND_P$7") (pintype "bidirectional"))
      (node (ref "U5") (pin "2") (pinfunction "GND_2") (pintype "input"))
      (node (ref "U6") (pin "2") (pinfunction "GND_2") (pintype "bidirectional"))
      (node (ref "U7") (pin "2") (pinfunction "S_2") (pintype "passive"))
      (node (ref "U7") (pin "2@1") (pinfunction "PAD_2@1") (pintype "bidirectional"))
      (node (ref "U8") (pin "P$10") (pinfunction "GND_P$10") (pintype "bidirectional"))
      (node (ref "U8") (pin "P$2") (pinfunction "GND_P$2") (pintype "bidirectional"))
      (node (ref "U8") (pin "P$20") (pinfunction "GND_P$20") (pintype "bidirectional"))
      (node (ref "U9") (pin "4") (pinfunction "S_4") (pintype "bidirectional"))
      (node (ref "X1") (pin "2") (pinfunction "G2_2") (pintype "power_in"))
      (node (ref "X1") (pin "4") (pinfunction "G1_4") (pintype "power_in"))
      (node (ref "X2") (pin "2") (pinfunction "G2_2") (pintype "power_in"))
      (node (ref "X2") (pin "4") (pinfunction "G1_4") (pintype "power_in"))
    )
    (net (code "8") (name "GNSS_1PPS") (class "Default")
      (node (ref "U8") (pin "P$11") (pinfunction "TM_P$11") (pintype "bidirectional"))
      (node (ref "U9") (pin "5") (pinfunction "G_5") (pintype "bidirectional"))
    )
    (net (code "9") (name "GNSS_UART_TX") (class "Default")
      (node (ref "R15") (pin "1") (pinfunction "1_1") (pintype "passive"))
      (node (ref "U8") (pin "P$15") (pinfunction "TX_P$15") (pintype "bidirectional"))
      (node (ref "U9") (pin "1") (pinfunction "S_1") (pintype "bidirectional"))
    )
    (net (code "10") (name "I2C_SCL") (class "Default")
      (node (ref "U13") (pin "29") (pinfunction "PB6_29") (pintype "bidirectional"))
      (node (ref "U6") (pin "1") (pinfunction "SCL_1") (pintype "bidirectional"))
    )
    (net (code "11") (name "I2C_SDA") (class "Default")
      (node (ref "U13") (pin "30") (pinfunction "PB7_30") (pintype "bidirectional"))
      (node (ref "U6") (pin "3") (pinfunction "SDA_3") (pintype "bidirectional"))
    )
    (net (code "12") (name "MCU_GNSS_1PPS") (class "Default")
      (node (ref "U13") (pin "8") (pinfunction "PA2_8") (pintype "bidirectional"))
      (node (ref "U9") (pin "3") (pinfunction "D_3") (pintype "bidirectional"))
    )
    (net (code "13") (name "MCU_GNSS_UART_RX") (class "Default")
      (node (ref "R16") (pin "1") (pinfunction "1_1") (pintype "passive"))
      (node (ref "U13") (pin "9") (pinfunction "PA3_9") (pintype "bidirectional"))
      (node (ref "U9") (pin "6") (pinfunction "D_6") (pintype "bidirectional"))
    )
    (net (code "14") (name "MCU_UART_RX") (class "Default")
      (node (ref "J1") (pin "3") (pinfunction "1_3") (pintype "passive"))
      (node (ref "RX") (pin "TP") (pinfunction "TP_TP") (pintype "input"))
      (node (ref "U13") (pin "20") (pinfunction "PA10_20") (pintype "bidirectional"))
    )
    (net (code "15") (name "MCU_UART_TX") (class "Default")
      (node (ref "J1") (pin "2") (pinfunction "1_2") (pintype "passive"))
      (node (ref "TX") (pin "TP") (pinfunction "TP_TP") (pintype "input"))
      (node (ref "U13") (pin "19") (pinfunction "PA9_19") (pintype "bidirectional"))
    )
    (net (code "16") (name "MISO") (class "Default")
      (node (ref "U11") (pin "13") (pinfunction "SDO_13") (pintype "output"))
      (node (ref "U12") (pin "13") (pinfunction "SDO_13") (pintype "output"))
      (node (ref "U13") (pin "12") (pinfunction "PA6_12") (pintype "bidirectional"))
    )
    (net (code "17") (name "MOSI") (class "Default")
      (node (ref "U11") (pin "14") (pinfunction "SDI_14") (pintype "input"))
      (node (ref "U12") (pin "14") (pinfunction "SDI_14") (pintype "input"))
      (node (ref "U13") (pin "13") (pinfunction "PA7_13") (pintype "bidirectional"))
    )
    (net (code "18") (name "NRST") (class "Default")
      (node (ref "JLINK") (pin "2") (pinfunction "2_2") (pintype "passive"))
      (node (ref "NRST") (pin "TP") (pinfunction "TP_TP") (pintype "input"))
      (node (ref "U13") (pin "4") (pinfunction "NRST_4") (pintype "bidirectional"))
    )
    (net (code "19") (name "Net-(C11-Pad1)") (class "Default")
      (node (ref "C11") (pin "1") (pinfunction "1_1") (pintype "passive"))
      (node (ref "L17") (pin "P$2") (pinfunction "P$2_P$2") (pintype "bidirectional"))
      (node (ref "R11") (pin "1") (pinfunction "1_1") (pintype "passive"))
      (node (ref "R12") (pin "2") (pinfunction "2_2") (pintype "passive"))
    )
    (net (code "20") (name "Net-(C21-Pad1)") (class "Default")
      (node (ref "C21") (pin "1") (pinfunction "1_1") (pintype "passive"))
      (node (ref "L5") (pin "1") (pinfunction "1_1") (pintype "passive"))
      (node (ref "R22") (pin "1") (pinfunction "1_1") (pintype "passive"))
    )
    (net (code "21") (name "Net-(C22-PadP$2)") (class "Default")
      (node (ref "C22") (pin "P$2") (pinfunction "P$2_P$2") (pintype "bidirectional"))
      (node (ref "L1") (pin "P$1") (pinfunction "P$1_P$1") (pintype "bidirectional"))
    )
    (net (code "22") (name "Net-(C23-Pad1)") (class "Default")
      (node (ref "C23") (pin "1") (pinfunction "1_1") (pintype "passive"))
      (node (ref "L1") (pin "P$2") (pinfunction "P$2_P$2") (pintype "bidirectional"))
      (node (ref "L6") (pin "P$1") (pinfunction "P$1_P$1") (pintype "bidirectional"))
    )
    (net (code "23") (name "Net-(C24-Pad1)") (class "Default")
      (node (ref "C24") (pin "1") (pinfunction "1_1") (pintype "passive"))
      (node (ref "L6") (pin "P$2") (pinfunction "P$2_P$2") (pintype "bidirectional"))
      (node (ref "L7") (pin "P$1") (pinfunction "P$1_P$1") (pintype "bidirectional"))
    )
    (net (code "24") (name "Net-(C25-Pad1)") (class "Default")
      (node (ref "C25") (pin "1") (pinfunction "1_1") (pintype "passive"))
      (node (ref "L11") (pin "P$1") (pinfunction "P$1_P$1") (pintype "bidirectional"))
      (node (ref "L7") (pin "P$2") (pinfunction "P$2_P$2") (pintype "bidirectional"))
    )
    (net (code "25") (name "Net-(C29-Pad2)") (class "Default")
      (node (ref "C29") (pin "2") (pinfunction "2_2") (pintype "passive"))
      (node (ref "C43") (pin "1") (pinfunction "1_1") (pintype "passive"))
      (node (ref "C45") (pin "1") (pinfunction "1_1") (pintype "passive"))
      (node (ref "L18") (pin "P$1") (pinfunction "P$1_P$1") (pintype "bidirectional"))
    )
    (net (code "26") (name "Net-(C30-Pad1)") (class "Default")
      (node (ref "C30") (pin "1") (pinfunction "1_1") (pintype "passive"))
      (node (ref "C41") (pin "1") (pinfunction "1_1") (pintype "passive"))
      (node (ref "L17") (pin "P$1") (pinfunction "P$1_P$1") (pintype "bidirectional"))
      (node (ref "L18") (pin "P$2") (pinfunction "P$2_P$2") (pintype "bidirectional"))
      (node (ref "L3") (pin "P$1") (pinfunction "P$1_P$1") (pintype "bidirectional"))
    )
    (net (code "27") (name "Net-(C33-Pad2)") (class "Default")
      (node (ref "C33") (pin "2") (pinfunction "2_2") (pintype "passive"))
      (node (ref "C35") (pin "1") (pinfunction "1_1") (pintype "passive"))
      (node (ref "C40") (pin "2") (pinfunction "2_2") (pintype "passive"))
      (node (ref "L16") (pin "2") (pinfunction "2_2") (pintype "passive"))
    )
    (net (code "28") (name "Net-(C35-Pad2)") (class "Default")
      (node (ref "C35") (pin "2") (pinfunction "2_2") (pintype "passive"))
      (node (ref "L14") (pin "2") (pinfunction "2_2") (pintype "passive"))
    )
    (net (code "29") (name "Net-(C36-Pad1)") (class "Default")
      (node (ref "C36") (pin "1") (pinfunction "1_1") (pintype "passive"))
      (node (ref "L10") (pin "1") (pinfunction "1_1") (pintype "passive"))
      (node (ref "L9") (pin "2") (pinfunction "2_2") (pintype "passive"))
    )
    (net (code "30") (name "Net-(C40-Pad1)") (class "Default")
      (node (ref "C40") (pin "1") (pinfunction "1_1") (pintype "passive"))
      (node (ref "L15") (pin "1") (pinfunction "1_1") (pintype "passive"))
    )
    (net (code "31") (name "Net-(C42-Pad1)") (class "Default")
      (node (ref "C42") (pin "1") (pinfunction "1_1") (pintype "passive"))
      (node (ref "C47") (pin "1") (pinfunction "1_1") (pintype "passive"))
      (node (ref "L10") (pin "2") (pinfunction "2_2") (pintype "passive"))
      (node (ref "L19") (pin "1") (pinfunction "1_1") (pintype "passive"))
    )
    (net (code "32") (name "Net-(C44-Pad1)") (class "Default")
      (node (ref "C44") (pin "1") (pinfunction "1_1") (pintype "passive"))
      (node (ref "C47") (pin "2") (pinfunction "2_2") (pintype "passive"))
      (node (ref "L19") (pin "2") (pinfunction "2_2") (pintype "passive"))
    )
    (net (code "33") (name "Net-(D2-PadA)") (class "Default")
      (node (ref "D2") (pin "A") (pinfunction "A_A") (pintype "passive"))
      (node (ref "J1") (pin "1") (pinfunction "1_1") (pintype "passive"))
      (node (ref "V_IN") (pin "TP") (pinfunction "TP_TP") (pintype "input"))
    )
    (net (code "34") (name "Net-(D2-PadC)") (class "Default")
      (node (ref "D2") (pin "C") (pinfunction "C_C") (pintype "passive"))
      (node (ref "F1") (pin "1") (pinfunction "1_1") (pintype "passive"))
    )
    (net (code "35") (name "Net-(J$1-SIGNAL)") (class "Default")
      (node (ref "J$1") (pin "SIG") (pinfunction "SIGNAL_SIG") (pintype "bidirectional"))
      (node (ref "U15") (pin "P$2") (pinfunction "RF1_P$2") (pintype "bidirectional"))
    )
    (net (code "36") (name "Net-(U1-BS)") (class "Default")
      (node (ref "C2") (pin "1") (pinfunction "1_1") (pintype "passive"))
      (node (ref "U1") (pin "1") (pinfunction "BS_1") (pintype "bidirectional"))
    )
    (net (code "37") (name "Net-(U1-EN)") (class "Default")
      (node (ref "C3") (pin "1") (pinfunction "1_1") (pintype "passive"))
      (node (ref "L2") (pin "P$1") (pinfunction "P$1_P$1") (pintype "bidirectional"))
      (node (ref "U1") (pin "4") (pinfunction "EN_4") (pintype "bidirectional"))
      (node (ref "U1") (pin "5") (pinfunction "IN_5") (pintype "bidirectional"))
    )
    (net (code "38") (name "Net-(U1-FB)") (class "Default")
      (node (ref "R1") (pin "1") (pinfunction "1_1") (pintype "passive"))
      (node (ref "R2") (pin "2") (pinfunction "2_2") (pintype "passive"))
      (node (ref "U1") (pin "3") (pinfunction "FB_3") (pintype "bidirectional"))
    )
    (net (code "39") (name "Net-(U1-SW)") (class "Default")
      (node (ref "C2") (pin "2") (pinfunction "2_2") (pintype "passive"))
      (node (ref "D1") (pin "C") (pinfunction "C_C") (pintype "passive"))
      (node (ref "L12") (pin "P$1") (pinfunction "P$1_P$1") (pintype "bidirectional"))
      (node (ref "U1") (pin "6") (pinfunction "SW_6") (pintype "bidirectional"))
    )
    (net (code "40") (name "Net-(U3-ADJ)") (class "Default")
      (node (ref "R4") (pin "2") (pinfunction "2_2") (pintype "passive"))
      (node (ref "R5") (pin "1") (pinfunction "1_1") (pintype "passive"))
      (node (ref "U3") (pin "P$2") (pinfunction "ADJ_P$2") (pintype "bidirectional"))
    )
    (net (code "41") (name "Net-(U7-D)") (class "Default")
      (node (ref "C37") (pin "1") (pinfunction "1_1") (pintype "passive"))
      (node (ref "C39") (pin "1") (pinfunction "1_1") (pintype "passive"))
      (node (ref "L4") (pin "2") (pinfunction "2_2") (pintype "passive"))
      (node (ref "L9") (pin "1") (pinfunction "1_1") (pintype "passive"))
      (node (ref "U7") (pin "3") (pinfunction "D_3") (pintype "passive"))
    )
    (net (code "42") (name "Net-(U7-G)") (class "Default")
      (node (ref "L3") (pin "P$2") (pinfunction "P$2_P$2") (pintype "bidirectional"))
      (node (ref "U7") (pin "1") (pinfunction "G_1") (pintype "passive"))
    )
    (net (code "43") (name "Net-(U8-GPIO6)") (class "Default")
      (node (ref "R14") (pin "1") (pinfunction "1_1") (pintype "passive"))
      (node (ref "U8") (pin "P$13") (pinfunction "GPIO6_P$13") (pintype "bidirectional"))
    )
    (net (code "44") (name "Net-(U10-RF)") (class "Default")
      (node (ref "U10") (pin "P$1") (pinfunction "RF_P$1") (pintype "bidirectional"))
      (node (ref "U8") (pin "P$1") (pinfunction "RF_IN_P$1") (pintype "bidirectional"))
    )
    (net (code "45") (name "Net-(U11-RXN)") (class "Default")
      (node (ref "C19") (pin "2") (pinfunction "2_2") (pintype "passive"))
      (node (ref "L8") (pin "2") (pinfunction "2_2") (pintype "passive"))
      (node (ref "U11") (pin "3") (pinfunction "RXN_3") (pintype "input"))
    )
    (net (code "46") (name "Net-(U11-RXP)") (class "Default")
      (node (ref "C18") (pin "1") (pinfunction "1_1") (pintype "passive"))
      (node (ref "L8") (pin "1") (pinfunction "1_1") (pintype "passive"))
      (node (ref "U11") (pin "2") (pinfunction "RXP_2") (pintype "input"))
    )
    (net (code "47") (name "Net-(U11-TX)") (class "Default")
      (node (ref "C22") (pin "P$1") (pinfunction "P$1_P$1") (pintype "bidirectional"))
      (node (ref "L5") (pin "2") (pinfunction "2_2") (pintype "passive"))
      (node (ref "U11") (pin "4") (pinfunction "TX_4") (pintype "output"))
    )
    (net (code "48") (name "Net-(U11-XIN)") (class "Default")
      (node (ref "U11") (pin "17") (pinfunction "XIN_17") (pintype "input"))
      (node (ref "X1") (pin "3") (pinfunction "X2_3") (pintype "bidirectional"))
    )
    (net (code "49") (name "Net-(U11-XOUT)") (class "Default")
      (node (ref "U11") (pin "16") (pinfunction "XOUT_16") (pintype "bidirectional"))
      (node (ref "X1") (pin "1") (pinfunction "X1_1") (pintype "bidirectional"))
    )
    (net (code "50") (name "Net-(U12-RXN)") (class "Default")
      (node (ref "C31") (pin "2") (pinfunction "2_2") (pintype "passive"))
      (node (ref "L13") (pin "2") (pinfunction "2_2") (pintype "passive"))
      (node (ref "U12") (pin "3") (pinfunction "RXN_3") (pintype "input"))
    )
    (net (code "51") (name "Net-(U12-RXP)") (class "Default")
      (node (ref "C20") (pin "1") (pinfunction "1_1") (pintype "passive"))
      (node (ref "L13") (pin "1") (pinfunction "1_1") (pintype "passive"))
      (node (ref "U12") (pin "2") (pinfunction "RXP_2") (pintype "input"))
    )
    (net (code "52") (name "Net-(U12-XIN)") (class "Default")
      (node (ref "U12") (pin "17") (pinfunction "XIN_17") (pintype "input"))
      (node (ref "X2") (pin "3") (pinfunction "X2_3") (pintype "bidirectional"))
    )
    (net (code "53") (name "Net-(U12-XOUT)") (class "Default")
      (node (ref "U12") (pin "16") (pinfunction "XOUT_16") (pintype "bidirectional"))
      (node (ref "X2") (pin "1") (pinfunction "X1_1") (pintype "bidirectional"))
    )
    (net (code "54") (name "Net-(U15-CTRL)") (class "Default")
      (node (ref "R19") (pin "1") (pinfunction "1_1") (pintype "passive"))
      (node (ref "R20") (pin "2") (pinfunction "2_2") (pintype "passive"))
      (node (ref "U15") (pin "P$7") (pinfunction "CTRL_P$7") (pintype "bidirectional"))
    )
    (net (code "55") (name "PA_IN") (class "Default")
      (node (ref "C29") (pin "1") (pinfunction "1_1") (pintype "passive"))
      (node (ref "L11") (pin "P$2") (pinfunction "P$2_P$2") (pintype "bidirectional"))
    )
    (net (code "56") (name "PA_OUT") (class "Default")
      (node (ref "C44") (pin "2") (pinfunction "2_2") (pintype "passive"))
      (node (ref "U15") (pin "P$5") (pinfunction "RF3_P$5") (pintype "bidirectional"))
    )
    (net (code "57") (name "RF_IN") (class "Default")
      (node (ref "L14") (pin "1") (pinfunction "1_1") (pintype "passive"))
      (node (ref "U15") (pin "P$11") (pinfunction "RF2_P$11") (pintype "bidirectional"))
    )
    (net (code "58") (name "RX_EN") (class "Default")
      (node (ref "R19") (pin "2") (pinfunction "2_2") (pintype "passive"))
      (node (ref "U13") (pin "2") (pinfunction "OSC_IN/PC14_2") (pintype "bidirectional"))
    )
    (net (code "59") (name "RX_IC_CLK") (class "Default")
      (node (ref "U12") (pin "20") (pinfunction "GPIO3_20") (pintype "bidirectional"))
      (node (ref "U13") (pin "26") (pinfunction "PB3_26") (pintype "bidirectional"))
    )
    (net (code "60") (name "RX_IC_DATA") (class "Default")
      (node (ref "U12") (pin "10") (pinfunction "GPIO1_10") (pintype "bidirectional"))
      (node (ref "U13") (pin "27") (pinfunction "PB4_27") (pintype "bidirectional"))
    )
    (net (code "61") (name "RX_IN") (class "Default")
      (node (ref "C18") (pin "2") (pinfunction "2_2") (pintype "passive"))
      (node (ref "C20") (pin "2") (pinfunction "2_2") (pintype "passive"))
      (node (ref "L15") (pin "2") (pinfunction "2_2") (pintype "passive"))
    )
    (net (code "62") (name "SCK") (class "Default")
      (node (ref "U11") (pin "12") (pinfunction "SCLK_12") (pintype "input"))
      (node (ref "U12") (pin "12") (pinfunction "SCLK_12") (pintype "input"))
      (node (ref "U13") (pin "11") (pinfunction "PA5_11") (pintype "bidirectional"))
    )
    (net (code "63") (name "SDN1") (class "Default")
      (node (ref "U11") (pin "1") (pinfunction "SDN_1") (pintype "input"))
      (node (ref "U13") (pin "14") (pinfunction "PB0_14") (pintype "bidirectional"))
    )
    (net (code "64") (name "SDN2") (class "Default")
      (node (ref "U12") (pin "1") (pinfunction "SDN_1") (pintype "input"))
      (node (ref "U13") (pin "25") (pinfunction "PA15_25") (pintype "bidirectional"))
    )
    (net (code "65") (name "SWCLK") (class "Default")
      (node (ref "JLINK") (pin "3") (pinfunction "3_3") (pintype "passive"))
      (node (ref "SWCLK") (pin "TP") (pinfunction "TP_TP") (pintype "input"))
      (node (ref "U13") (pin "24") (pinfunction "PA14_24") (pintype "bidirectional"))
    )
    (net (code "66") (name "SWDIO") (class "Default")
      (node (ref "JLINK") (pin "4") (pinfunction "4_4") (pintype "passive"))
      (node (ref "SWDIO") (pin "TP") (pinfunction "TP_TP") (pintype "input"))
      (node (ref "U13") (pin "23") (pinfunction "PA13_23") (pintype "bidirectional"))
    )
    (net (code "67") (name "TRX_IC_CLOCK") (class "Default")
      (node (ref "U11") (pin "19") (pinfunction "GPIO2_19") (pintype "bidirectional"))
      (node (ref "U13") (pin "7") (pinfunction "PA1_7") (pintype "bidirectional"))
    )
    (net (code "68") (name "TRX_IC_DATA") (class "Default")
      (node (ref "U11") (pin "10") (pinfunction "GPIO1_10") (pintype "bidirectional"))
      (node (ref "U13") (pin "15") (pinfunction "PB1_15") (pintype "bidirectional"))
    )
    (net (code "69") (name "TX_CTRL") (class "Default")
      (node (ref "R11") (pin "2") (pinfunction "2_2") (pintype "passive"))
      (node (ref "U13") (pin "28") (pinfunction "PB5_28") (pintype "bidirectional"))
    )
    (net (code "70") (name "V_BAT") (class "Default")
      (node (ref "C4") (pin "1") (pinfunction "11_1") (pintype "passive"))
      (node (ref "C6") (pin "1") (pinfunction "1_1") (pintype "passive"))
      (node (ref "F1") (pin "2") (pinfunction "2_2") (pintype "passive"))
      (node (ref "L2") (pin "P$2") (pinfunction "P$2_P$2") (pintype "bidirectional"))
      (node (ref "U3") (pin "P$5") (pinfunction "EN_P$5") (pintype "bidirectional"))
      (node (ref "U3") (pin "P$6") (pinfunction "VIN_P$6") (pintype "bidirectional"))
    )
    (net (code "71") (name "V_PA") (class "Default")
      (node (ref "C7") (pin "1") (pinfunction "1_1") (pintype "passive"))
      (node (ref "L4") (pin "1") (pinfunction "1_1") (pintype "passive"))
      (node (ref "R5") (pin "2") (pinfunction "2_2") (pintype "passive"))
      (node (ref "U3") (pin "P$1") (pinfunction "VOUT_P$1") (pintype "bidirectional"))
      (node (ref "V_PA") (pin "TP") (pinfunction "TP_TP") (pintype "input"))
    )
    (net (code "72") (name "unconnected-(U3-PG-PadP$3)") (class "Default")
      (node (ref "U3") (pin "P$3") (pinfunction "PG_P$3") (pintype "bidirectional"))
    )
    (net (code "73") (name "unconnected-(U5-BP-Pad4)") (class "Default")
      (node (ref "U5") (pin "4") (pinfunction "BP_4") (pintype "input"))
    )
    (net (code "74") (name "unconnected-(U8-BOOTSEL-PadP$9)") (class "Default")
      (node (ref "U8") (pin "P$9") (pinfunction "BOOTSEL_P$9") (pintype "bidirectional"))
    )
    (net (code "75") (name "unconnected-(U8-GPIO0-PadP$18)") (class "Default")
      (node (ref "U8") (pin "P$18") (pinfunction "GPIO0_P$18") (pintype "bidirectional"))
    )
    (net (code "76") (name "unconnected-(U8-GPIO1-PadP$17)") (class "Default")
      (node (ref "U8") (pin "P$17") (pinfunction "GPIO1_P$17") (pintype "bidirectional"))
    )
    (net (code "77") (name "unconnected-(U8-GPIO7-PadP$12)") (class "Default")
      (node (ref "U8") (pin "P$12") (pinfunction "GPIO7_P$12") (pintype "bidirectional"))
    )
    (net (code "78") (name "unconnected-(U8-GPIO8-PadP$5)") (class "Default")
      (node (ref "U8") (pin "P$5") (pinfunction "GPIO8_P$5") (pintype "bidirectional"))
    )
    (net (code "79") (name "unconnected-(U8-NC-PadP$4)") (class "Default")
      (node (ref "U8") (pin "P$4") (pinfunction "NC_P$4") (pintype "bidirectional"))
    )
    (net (code "80") (name "unconnected-(U8-NC-PadP$16)") (class "Default")
      (node (ref "U8") (pin "P$16") (pinfunction "NC_P$16") (pintype "bidirectional"))
    )
    (net (code "81") (name "unconnected-(U8-NRESET-PadP$8)") (class "Default")
      (node (ref "U8") (pin "P$8") (pinfunction "NRESET_P$8") (pintype "bidirectional"))
    )
    (net (code "82") (name "unconnected-(U8-RX-PadP$14)") (class "Default")
      (node (ref "U8") (pin "P$14") (pinfunction "RX_P$14") (pintype "bidirectional"))
    )
    (net (code "83") (name "unconnected-(U8-SYS_ON-PadP$7)") (class "Default")
      (node (ref "U8") (pin "P$7") (pinfunction "SYS_ON_P$7") (pintype "bidirectional"))
    )
    (net (code "84") (name "unconnected-(U10-PAD-PadP$2)") (class "Default")
      (node (ref "U10") (pin "P$2") (pinfunction "PAD_P$2") (pintype "bidirectional"))
    )
    (net (code "85") (name "unconnected-(U11-GNDX-Pad18)") (class "Default")
      (node (ref "U11") (pin "18") (pinfunction "GNDX_18") (pintype "bidirectional"))
    )
    (net (code "86") (name "unconnected-(U11-GPIO0-Pad9)") (class "Default")
      (node (ref "U11") (pin "9") (pinfunction "GPIO0_9") (pintype "bidirectional"))
    )
    (net (code "87") (name "unconnected-(U11-GPIO3-Pad20)") (class "Default")
      (node (ref "U11") (pin "20") (pinfunction "GPIO3_20") (pintype "bidirectional"))
    )
    (net (code "88") (name "unconnected-(U11-NIRQ-Pad11)") (class "Default")
      (node (ref "U11") (pin "11") (pinfunction "NIRQ_11") (pintype "bidirectional"))
    )
    (net (code "89") (name "unconnected-(U11-TXRAMP-Pad7)") (class "Default")
      (node (ref "U11") (pin "7") (pinfunction "TXRAMP_7") (pintype "bidirectional"))
    )
    (net (code "90") (name "unconnected-(U12-GNDX-Pad18)") (class "Default")
      (node (ref "U12") (pin "18") (pinfunction "GNDX_18") (pintype "bidirectional"))
    )
    (net (code "91") (name "unconnected-(U12-GPIO0-Pad9)") (class "Default")
      (node (ref "U12") (pin "9") (pinfunction "GPIO0_9") (pintype "bidirectional"))
    )
    (net (code "92") (name "unconnected-(U12-GPIO2-Pad19)") (class "Default")
      (node (ref "U12") (pin "19") (pinfunction "GPIO2_19") (pintype "bidirectional"))
    )
    (net (code "93") (name "unconnected-(U12-NIRQ-Pad11)") (class "Default")
      (node (ref "U12") (pin "11") (pinfunction "NIRQ_11") (pintype "bidirectional"))
    )
    (net (code "94") (name "unconnected-(U12-TX-Pad4)") (class "Default")
      (node (ref "U12") (pin "4") (pinfunction "TX_4") (pintype "output"))
    )
    (net (code "95") (name "unconnected-(U12-TXRAMP-Pad7)") (class "Default")
      (node (ref "U12") (pin "7") (pinfunction "TXRAMP_7") (pintype "bidirectional"))
    )
    (net (code "96") (name "unconnected-(U13-PA11-Pad21)") (class "Default")
      (node (ref "U13") (pin "21") (pinfunction "PA11_21") (pintype "bidirectional"))
    )
    (net (code "97") (name "unconnected-(U13-PA12-Pad22)") (class "Default")
      (node (ref "U13") (pin "22") (pinfunction "PA12_22") (pintype "bidirectional"))
    )
    (net (code "98") (name "~{EEPROM_WRITE_EN}") (class "Default")
      (node (ref "R6") (pin "2") (pinfunction "2_2") (pintype "passive"))
      (node (ref "U13") (pin "3") (pinfunction "OSC_OUT/PC15_3") (pintype "bidirectional"))
      (node (ref "U6") (pin "5") (pinfunction "WP_5") (pintype "bidirectional"))
    )
  )
)
